# PX4FMUv1_6.net
KiCad netlist of a schematic drawn in EAGLE
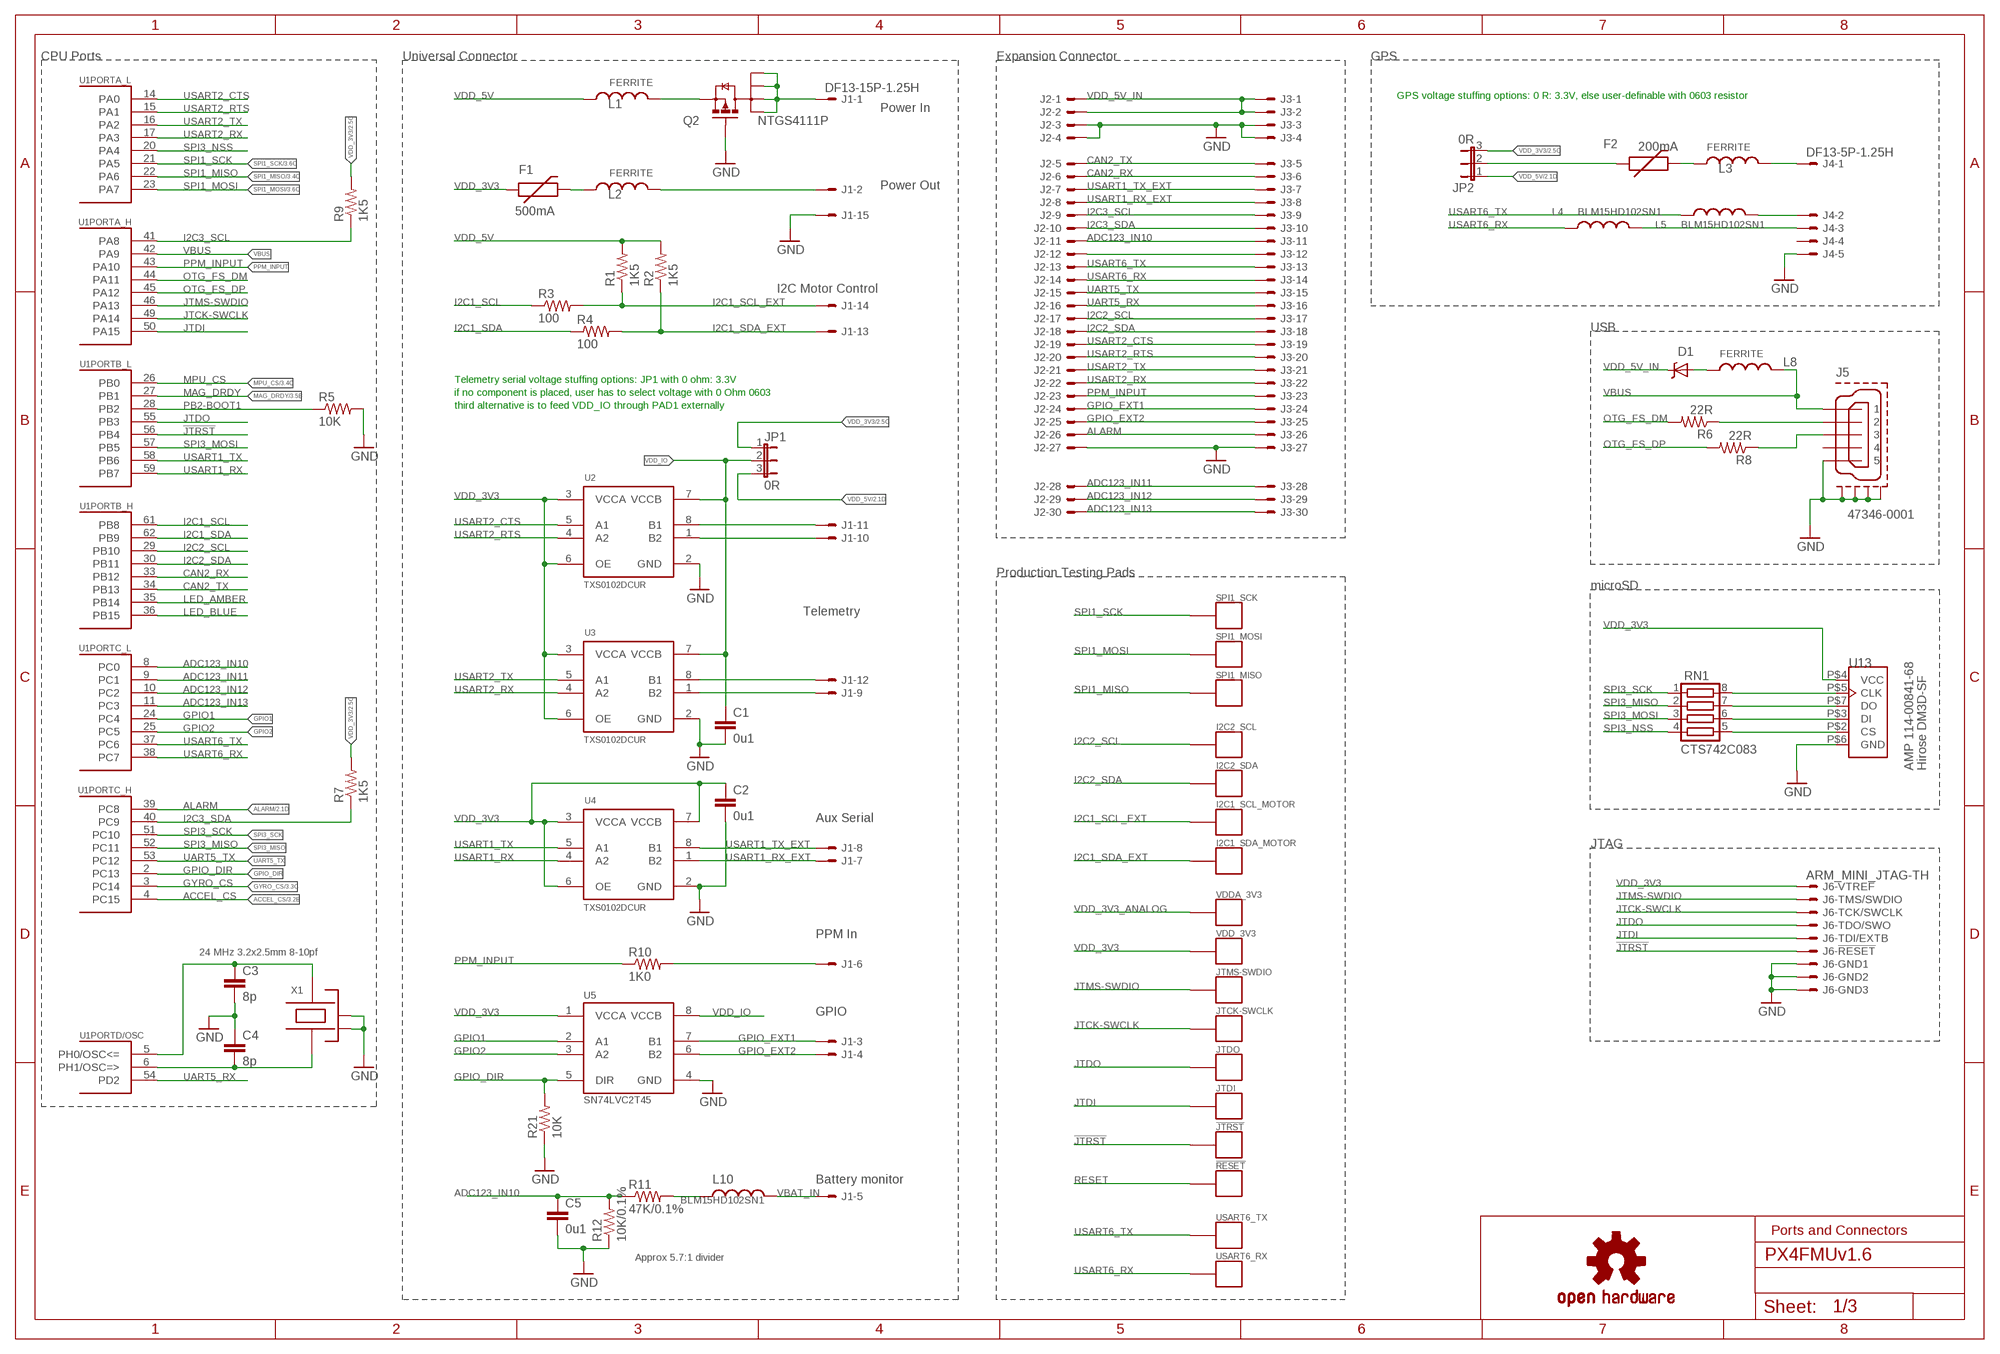
[diagram p0: schematic, sheet 1]
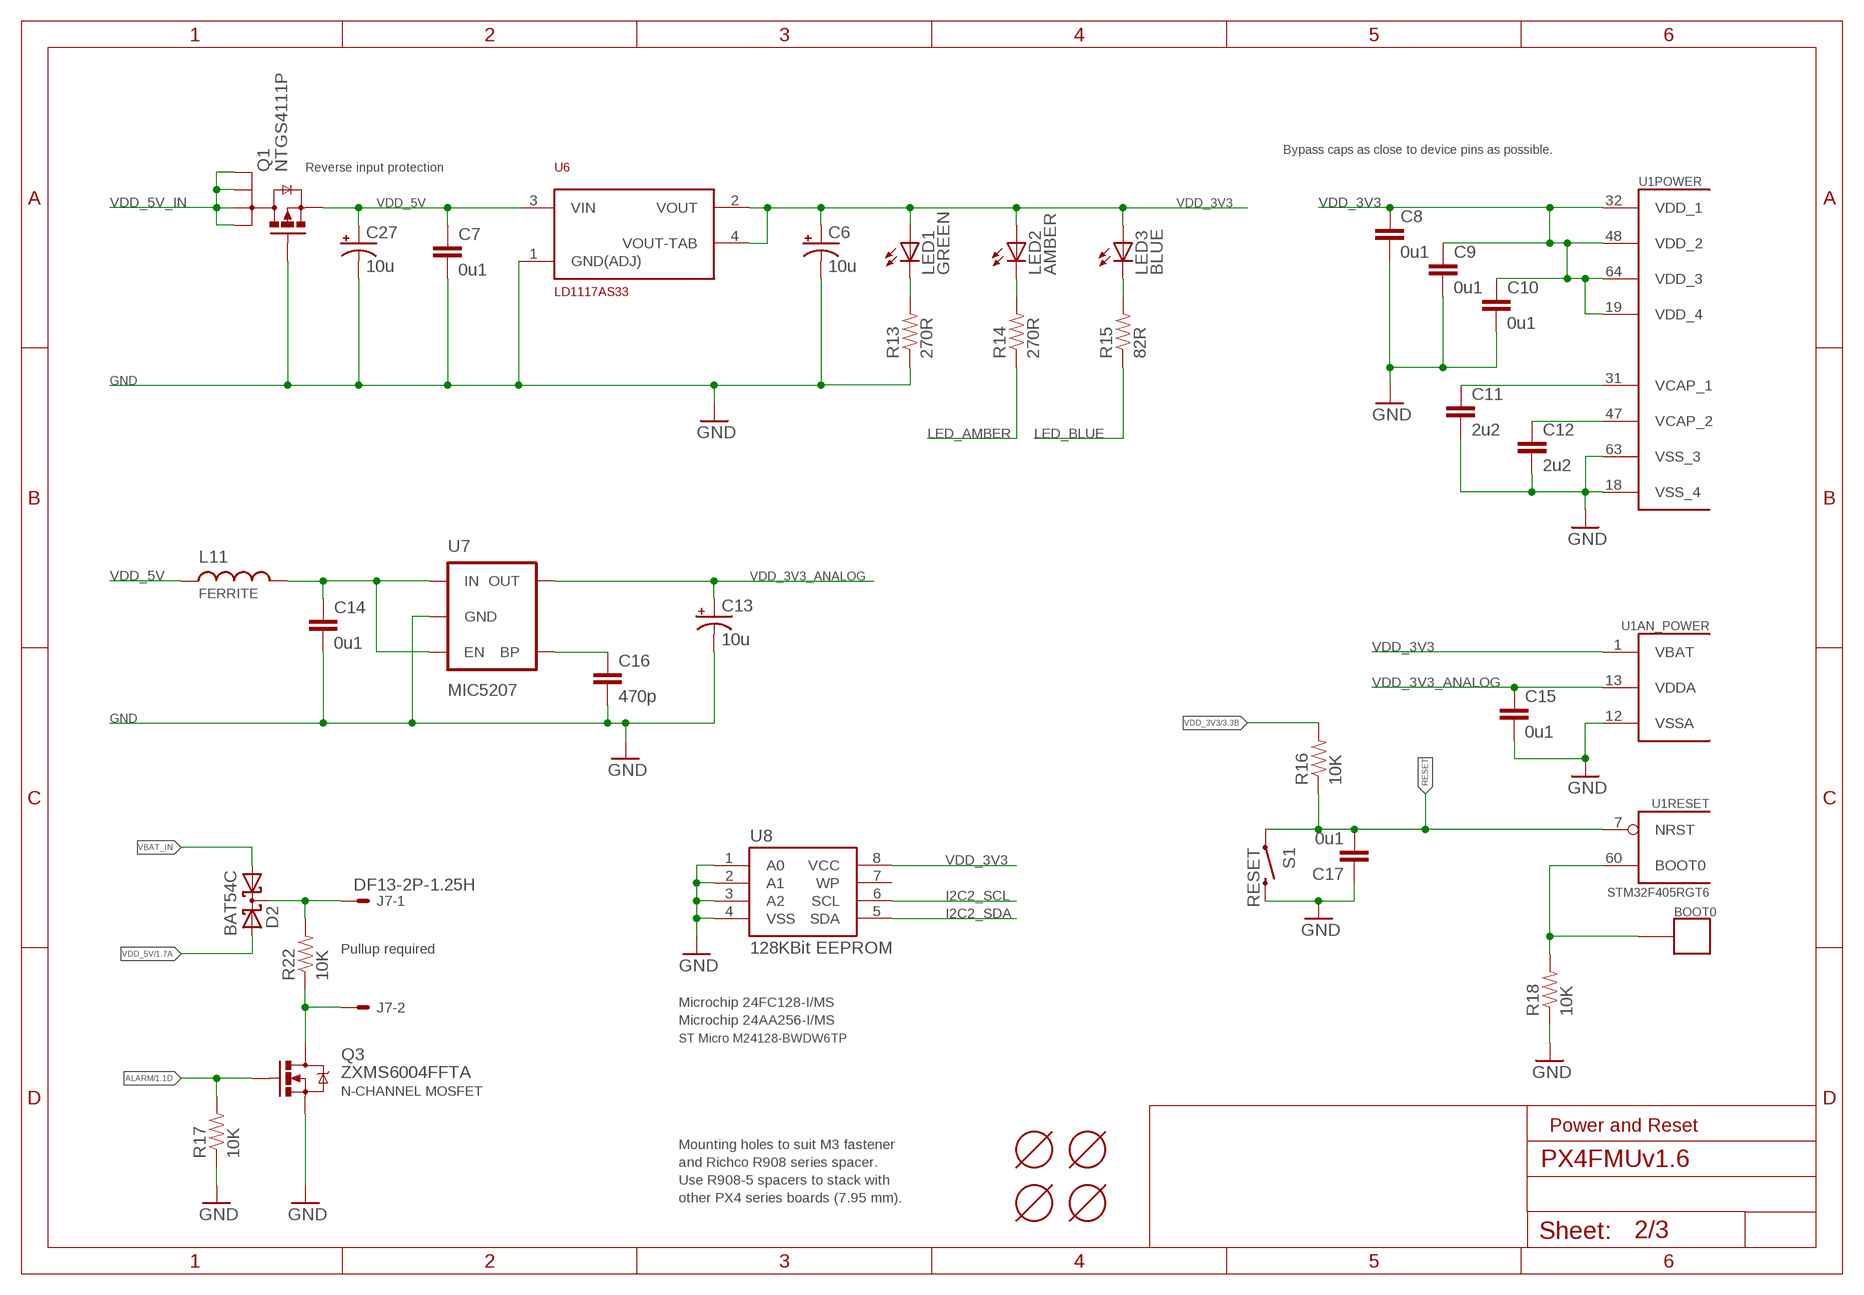
[diagram p1: schematic, sheet 2]
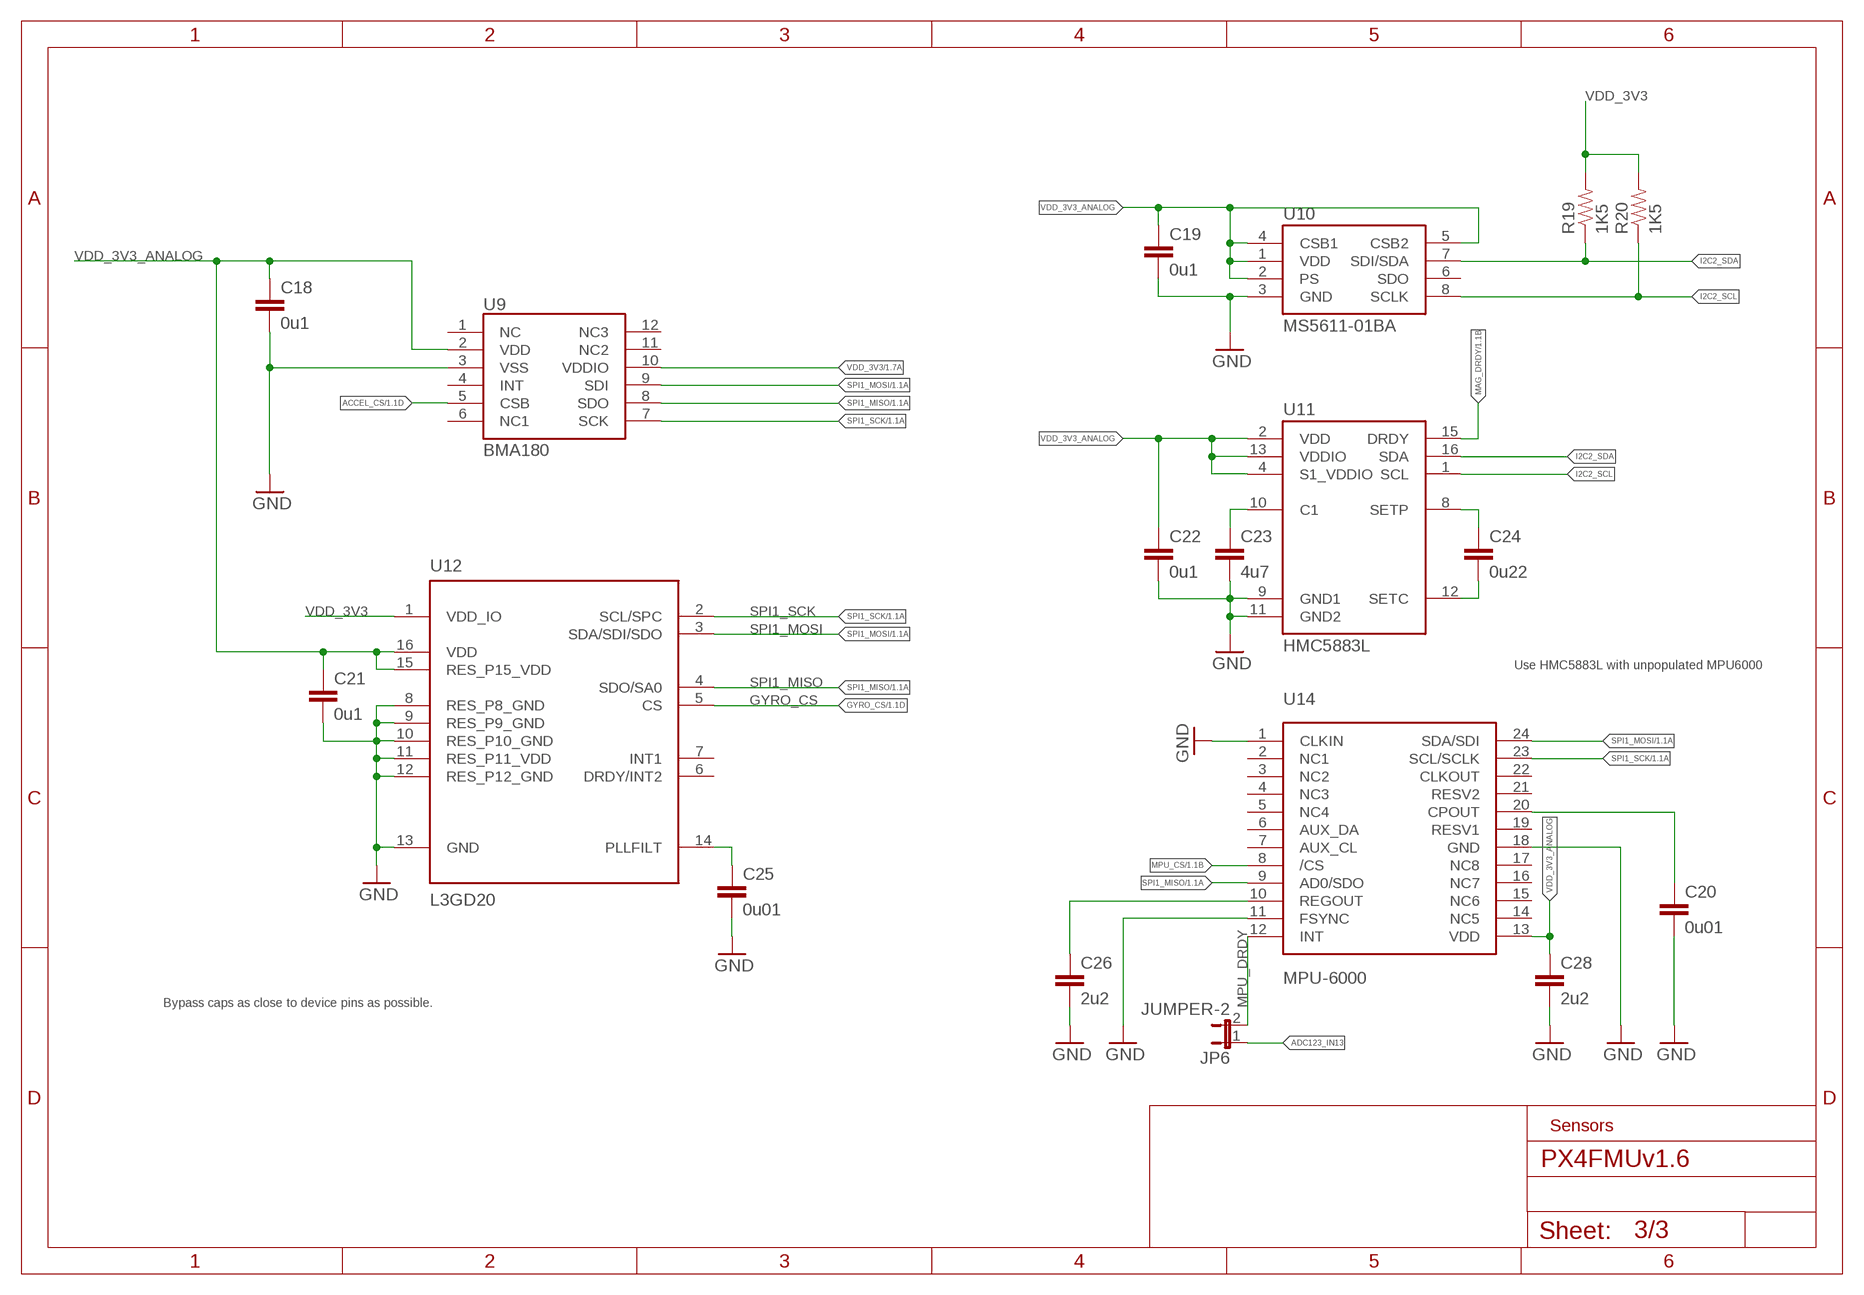
[diagram p2: schematic, sheet 3]

(export (version "E")
  (design (tool "Eeschema 10.0.6"))
  (components
    (comp (ref "!JTRST")
      (value "PAD.04")
      (footprint "eagle-import:PAD.04X.04")
      (libsource (lib "eagle-import") (part "PAD.04"))
    )
    (comp (ref "!RESET")
      (value "PAD.04")
      (footprint "eagle-import:PAD.04X.04")
      (libsource (lib "eagle-import") (part "PAD.04"))
    )
    (comp (ref "C1")
      (value "0u1")
      (footprint "eagle-import:0402-CAP")
      (fields (field (name "PARTNO") "CC0402ZRY5V7BB104"))
      (libsource (lib "eagle-import") (part "CAP0402-CAP"))
    )
    (comp (ref "C2")
      (value "0u1")
      (footprint "eagle-import:0402-CAP")
      (fields (field (name "PARTNO") "CC0402ZRY5V7BB104"))
      (libsource (lib "eagle-import") (part "CAP0402-CAP"))
    )
    (comp (ref "C3")
      (value "8p")
      (footprint "eagle-import:0402-CAP")
      (fields (field (name "PARTNO") "C1005C0G1H080C"))
      (libsource (lib "eagle-import") (part "CAP0402-CAP"))
    )
    (comp (ref "C4")
      (value "8p")
      (footprint "eagle-import:0402-CAP")
      (fields (field (name "PARTNO") "C1005C0G1H080C"))
      (libsource (lib "eagle-import") (part "CAP0402-CAP"))
    )
    (comp (ref "C5")
      (value "0u1")
      (footprint "eagle-import:0402-CAP")
      (fields (field (name "PARTNO") "CC0402ZRY5V7BB104"))
      (libsource (lib "eagle-import") (part "CAP0402-CAP"))
    )
    (comp (ref "D1")
      (value "MSS1P4-M3")
      (footprint "eagle-import:MICROSMP")
      (fields (field (name "PARTNO") "MSS1P4-M3/89A"))
      (libsource (lib "eagle-import") (part "DIODE-SCHOTTKY_MSMP"))
    )
    (comp (ref "F1")
      (value "500mA")
      (footprint "eagle-import:0402-PTC")
      (fields (field (name "PARTNO") "MF-FSMF050X-2"))
      (libsource (lib "eagle-import") (part "PTC0402"))
    )
    (comp (ref "F2")
      (value "200mA")
      (footprint "eagle-import:0402-PTC")
      (fields (field (name "PARTNO") "MF-FSMF020X-2"))
      (libsource (lib "eagle-import") (part "PTC0402"))
    )
    (comp (ref "I2C1_SCL_MOTOR")
      (value "PAD.03")
      (footprint "eagle-import:PAD.03X.03")
      (libsource (lib "eagle-import") (part "PAD.03"))
    )
    (comp (ref "I2C1_SDA_MOTOR")
      (value "PAD.03")
      (footprint "eagle-import:PAD.03X.03")
      (libsource (lib "eagle-import") (part "PAD.03"))
    )
    (comp (ref "I2C2_SCL")
      (value "PAD.03")
      (footprint "eagle-import:PAD.03X.03")
      (libsource (lib "eagle-import") (part "PAD.03"))
    )
    (comp (ref "I2C2_SDA")
      (value "PAD.04")
      (footprint "eagle-import:PAD.04X.04")
      (libsource (lib "eagle-import") (part "PAD.04"))
    )
    (comp (ref "J1")
      (value "DF13-15P-1.25H")
      (footprint "eagle-import:DF13A-15P-1.25H")
      (fields (field (name "PARTNO") "DF13A-15P-1.25H(20)"))
      (libsource (lib "eagle-import") (part "DF13-15P-1.25?H"))
    )
    (comp (ref "J2")
      (value "HEADER_2X15-REV")
      (footprint "eagle-import:HEADER_2MM_2X15_REVERSE")
      (fields (field (name "BOM") "EXCLUDE") (field (name "PARTNO") "953230-2000-AR-PR"))
      (libsource (lib "eagle-import") (part "HEADER_2X15-REV"))
    )
    (comp (ref "J3")
      (value "HEADER_2X15")
      (footprint "eagle-import:HEADER_2MM_2X15")
      (fields (field (name "PARTNO") "953230-2000-AR-PR"))
      (libsource (lib "eagle-import") (part "HEADER_2X15-SMD"))
    )
    (comp (ref "J4")
      (value "DF13-5P-1.25H")
      (footprint "eagle-import:DF13A-5P-1.25H")
      (fields (field (name "PARTNO") "DF13A-5P-1.25H(20)"))
      (libsource (lib "eagle-import") (part "DF13-5P-1.25?H"))
    )
    (comp (ref "J5")
      (value "47346-0001")
      (footprint "eagle-import:MOLEX-47346-0001")
      (libsource (lib "eagle-import") (part "MOLEX-47346-0001"))
    )
    (comp (ref "J6")
      (value "ARM_MINI_JTAG-TH")
      (footprint "eagle-import:FTSH-105-01-XXX-DV")
      (fields (field (name "PARTNO") "M50-3900542"))
      (libsource (lib "eagle-import") (part "ARM_MINI_JTAG-TH"))
    )
    (comp (ref "JP1")
      (value "0R")
      (footprint "eagle-import:SJ_3_0603_PASTE1&2")
      (fields (field (name "PARTNO") "RMCF0402ZT0R00"))
      (libsource (lib "eagle-import") (part "JUMPER-30603"))
    )
    (comp (ref "JP2")
      (value "0R")
      (footprint "eagle-import:SJ_3_0603_PASTE1&2")
      (fields (field (name "PARTNO") "RMCF0402ZT0R00"))
      (libsource (lib "eagle-import") (part "JUMPER-30603"))
    )
    (comp (ref "JTCK-SWCLK")
      (value "PAD.04")
      (footprint "eagle-import:PAD.04X.04")
      (libsource (lib "eagle-import") (part "PAD.04"))
    )
    (comp (ref "JTDI")
      (value "PAD.04")
      (footprint "eagle-import:PAD.04X.04")
      (libsource (lib "eagle-import") (part "PAD.04"))
    )
    (comp (ref "JTDO")
      (value "PAD.04")
      (footprint "eagle-import:PAD.04X.04")
      (libsource (lib "eagle-import") (part "PAD.04"))
    )
    (comp (ref "JTMS-SWDIO")
      (value "PAD.04")
      (footprint "eagle-import:PAD.04X.04")
      (libsource (lib "eagle-import") (part "PAD.04"))
    )
    (comp (ref "L1")
      (value "FERRITE")
      (footprint "eagle-import:0402-IND")
      (fields (field (name "PARTNO") "BKP1005HS121-T"))
      (libsource (lib "eagle-import") (part "INDUCTOR0402"))
    )
    (comp (ref "L2")
      (value "FERRITE")
      (footprint "eagle-import:0402-IND")
      (fields (field (name "PARTNO") "BKP1005HS121-T"))
      (libsource (lib "eagle-import") (part "INDUCTOR0402"))
    )
    (comp (ref "L3")
      (value "FERRITE")
      (footprint "eagle-import:0402-IND")
      (fields (field (name "PARTNO") "BKP1005HS121-T"))
      (libsource (lib "eagle-import") (part "INDUCTOR0402"))
    )
    (comp (ref "L4")
      (value "BLM15HD102SN1")
      (footprint "eagle-import:0402-IND")
      (libsource (lib "eagle-import") (part "INDUCTOR0402"))
    )
    (comp (ref "L5")
      (value "BLM15HD102SN1")
      (footprint "eagle-import:0402-IND")
      (libsource (lib "eagle-import") (part "INDUCTOR0402"))
    )
    (comp (ref "L8")
      (value "FERRITE")
      (footprint "eagle-import:0402-IND")
      (fields (field (name "PARTNO") "BKP1005HS121-T"))
      (libsource (lib "eagle-import") (part "INDUCTOR0402"))
    )
    (comp (ref "L10")
      (value "BLM15HD102SN1")
      (footprint "eagle-import:0402-IND")
      (libsource (lib "eagle-import") (part "INDUCTOR0402"))
    )
    (comp (ref "Q2")
      (value "NTGS4111P")
      (footprint "eagle-import:TSOP-6")
      (libsource (lib "eagle-import") (part "NTGS4111P"))
    )
    (comp (ref "R1")
      (value "1K5")
      (footprint "eagle-import:0402-RES")
      (fields (field (name "PARTNO") "RMCF0402JT1K50"))
      (libsource (lib "eagle-import") (part "RESISTOR0402-RES"))
    )
    (comp (ref "R2")
      (value "1K5")
      (footprint "eagle-import:0402-RES")
      (fields (field (name "PARTNO") "RMCF0402JT1K50"))
      (libsource (lib "eagle-import") (part "RESISTOR0402-RES"))
    )
    (comp (ref "R3")
      (value "100")
      (footprint "eagle-import:0402-RES")
      (fields (field (name "PARTNO") "RMCF0402JT100R"))
      (libsource (lib "eagle-import") (part "RESISTOR0402-RES"))
    )
    (comp (ref "R4")
      (value "100")
      (footprint "eagle-import:0402-RES")
      (fields (field (name "PARTNO") "RMCF0402JT100R"))
      (libsource (lib "eagle-import") (part "RESISTOR0402-RES"))
    )
    (comp (ref "R5")
      (value "10K")
      (footprint "eagle-import:0402-RES")
      (fields (field (name "PARTNO") "RMCF0402FT10K0"))
      (libsource (lib "eagle-import") (part "RESISTOR0402-RES"))
    )
    (comp (ref "R6")
      (value "22R")
      (footprint "eagle-import:0402-RES")
      (fields (field (name "PARTNO") "RMCF0402JT22R0"))
      (libsource (lib "eagle-import") (part "RESISTOR0402-RES"))
    )
    (comp (ref "R7")
      (value "1K5")
      (footprint "eagle-import:0402-RES")
      (fields (field (name "PARTNO") "RMCF0402JT1K50"))
      (libsource (lib "eagle-import") (part "RESISTOR0402-RES"))
    )
    (comp (ref "R8")
      (value "22R")
      (footprint "eagle-import:0402-RES")
      (fields (field (name "PARTNO") "RMCF0402JT22R0"))
      (libsource (lib "eagle-import") (part "RESISTOR0402-RES"))
    )
    (comp (ref "R9")
      (value "1K5")
      (footprint "eagle-import:0402-RES")
      (fields (field (name "PARTNO") "RMCF0402JT1K50"))
      (libsource (lib "eagle-import") (part "RESISTOR0402-RES"))
    )
    (comp (ref "R10")
      (value "1K0")
      (footprint "eagle-import:0402-RES")
      (fields (field (name "PARTNO") "RMCF0402JT1K00"))
      (libsource (lib "eagle-import") (part "RESISTOR0402-RES"))
    )
    (comp (ref "R11")
      (value "47K/0.1%")
      (footprint "eagle-import:0402-RES")
      (fields (field (name "PARTNO") "ERA-2AEB473X"))
      (libsource (lib "eagle-import") (part "RESISTOR0402-RES"))
    )
    (comp (ref "R12")
      (value "10K/0.1%")
      (footprint "eagle-import:0402-RES")
      (fields (field (name "PARTNO") "ERA-2AEB103X"))
      (libsource (lib "eagle-import") (part "RESISTOR0402-RES"))
    )
    (comp (ref "R21")
      (value "10K")
      (footprint "eagle-import:0402-RES")
      (fields (field (name "PARTNO") "RMCF0402FT10K0"))
      (libsource (lib "eagle-import") (part "RESISTOR0402-RES"))
    )
    (comp (ref "RN1")
      (value "CTS742C083")
      (footprint "eagle-import:CTS742C083")
      (fields (field (name "PARTNO") "TC164-JR-07100RL"))
      (libsource (lib "eagle-import") (part "CTS742C083"))
    )
    (comp (ref "SPI1_MISO")
      (value "PAD.04")
      (footprint "eagle-import:PAD.04X.04")
      (libsource (lib "eagle-import") (part "PAD.04"))
    )
    (comp (ref "SPI1_MOSI")
      (value "PAD.04")
      (footprint "eagle-import:PAD.04X.04")
      (libsource (lib "eagle-import") (part "PAD.04"))
    )
    (comp (ref "SPI1_SCK")
      (value "PAD.04")
      (footprint "eagle-import:PAD.04X.04")
      (libsource (lib "eagle-import") (part "PAD.04"))
    )
    (comp (ref "U$7")
      (value "OSHW-LOGOS")
      (footprint "eagle-import:OSHW-LOGO-S")
      (libsource (lib "eagle-import") (part "OSHW-LOGOS"))
    )
    (comp (ref "U1")
      (value "STM32F405RGT6")
      (footprint "eagle-import:TQFP64")
      (fields (field (name "PARTNO") "STM32F405RGT6"))
      (libsource (lib "eagle-import") (part "STM32F20X_TQFP64"))
    )
    (comp (ref "U2")
      (value "TXS0102DCUR")
      (footprint "eagle-import:TI-DCU")
      (libsource (lib "eagle-import") (part "TXS0102DCUR"))
    )
    (comp (ref "U3")
      (value "TXS0102DCUR")
      (footprint "eagle-import:TI-DCU")
      (libsource (lib "eagle-import") (part "TXS0102DCUR"))
    )
    (comp (ref "U4")
      (value "TXS0102DCUR")
      (footprint "eagle-import:TI-DCU")
      (libsource (lib "eagle-import") (part "TXS0102DCUR"))
    )
    (comp (ref "U5")
      (value "SN74LVC2T45")
      (footprint "eagle-import:TI-DCU")
      (libsource (lib "eagle-import") (part "SN74LVC2T45DCUR"))
    )
    (comp (ref "U13")
      (value "AMP 114-00841-68")
      (footprint "eagle-import:AMPHENOL_114-00841-68")
      (fields (field (name "PARTNO") "114-00841-68"))
      (libsource (lib "eagle-import") (part "SF-MICROSDAMP-114-00841-68"))
    )
    (comp (ref "USART6_RX")
      (value "PAD.04")
      (footprint "eagle-import:PAD.04X.04")
      (libsource (lib "eagle-import") (part "PAD.04"))
    )
    (comp (ref "USART6_TX")
      (value "PAD.04")
      (footprint "eagle-import:PAD.04X.04")
      (libsource (lib "eagle-import") (part "PAD.04"))
    )
    (comp (ref "VDDA_3V3")
      (value "PAD.04")
      (footprint "eagle-import:PAD.04X.04")
      (libsource (lib "eagle-import") (part "PAD.04"))
    )
    (comp (ref "VDD_3V3")
      (value "PAD.04")
      (footprint "eagle-import:PAD.04X.04")
      (libsource (lib "eagle-import") (part "PAD.04"))
    )
    (comp (ref "X1")
      (value "24 MHz 3.2x2.5mm 8-10pf")
      (footprint "eagle-import:OSCILLATOR-3.2X2.5")
      (fields (field (name "PARTNO") "NX3225SA-24.000000MHZ"))
      (libsource (lib "eagle-import") (part "OSCILLATOR-3.2X2.5"))
    )
    (comp (ref "C18")
      (value "0u1")
      (footprint "eagle-import:0402-CAP")
      (fields (field (name "PARTNO") "CC0402ZRY5V7BB104"))
      (libsource (lib "eagle-import") (part "CAP0402-CAP"))
    )
    (comp (ref "C19")
      (value "0u1")
      (footprint "eagle-import:0402-CAP")
      (fields (field (name "PARTNO") "CC0402ZRY5V7BB104"))
      (libsource (lib "eagle-import") (part "CAP0402-CAP"))
    )
    (comp (ref "C20")
      (value "0u01")
      (footprint "eagle-import:0402-CAP")
      (fields (field (name "PARTNO") "CC0402KRX7R7BB103"))
      (libsource (lib "eagle-import") (part "CAP0402-CAP"))
    )
    (comp (ref "C21")
      (value "0u1")
      (footprint "eagle-import:0402-CAP")
      (fields (field (name "PARTNO") "CC0402ZRY5V7BB104"))
      (libsource (lib "eagle-import") (part "CAP0402-CAP"))
    )
    (comp (ref "C22")
      (value "0u1")
      (footprint "eagle-import:0402-CAP")
      (fields (field (name "PARTNO") "CC0402ZRY5V7BB104"))
      (libsource (lib "eagle-import") (part "CAP0402-CAP"))
    )
    (comp (ref "C23")
      (value "4u7")
      (footprint "eagle-import:0402-CAP")
      (fields (field (name "PARTNO") "C1608Y5V0J475Z"))
      (libsource (lib "eagle-import") (part "CAP0402-CAP"))
    )
    (comp (ref "C24")
      (value "0u22")
      (footprint "eagle-import:0402-CAP")
      (fields (field (name "PARTNO") "C1005Y5V1C224Z"))
      (libsource (lib "eagle-import") (part "CAP0402-CAP"))
    )
    (comp (ref "C25")
      (value "0u01")
      (footprint "eagle-import:0402-CAP")
      (fields (field (name "PARTNO") "CC0402KRX7R7BB103"))
      (libsource (lib "eagle-import") (part "CAP0402-CAP"))
    )
    (comp (ref "C26")
      (value "2u2")
      (footprint "eagle-import:0402-CAP")
      (fields (field (name "PARTNO") "C1608Y5V1C225Z"))
      (libsource (lib "eagle-import") (part "CAP0402-CAP"))
    )
    (comp (ref "C28")
      (value "2u2")
      (footprint "eagle-import:0402-CAP")
      (fields (field (name "PARTNO") "C1608Y5V1C225Z"))
      (libsource (lib "eagle-import") (part "CAP0402-CAP"))
    )
    (comp (ref "JP6")
      (value "JUMPER-2")
      (footprint "eagle-import:SJ_2")
      (libsource (lib "eagle-import") (part "JUMPER-2"))
    )
    (comp (ref "R19")
      (value "1K5")
      (footprint "eagle-import:0402-RES")
      (fields (field (name "PARTNO") "RMCF0402JT1K50"))
      (libsource (lib "eagle-import") (part "RESISTOR0402-RES"))
    )
    (comp (ref "R20")
      (value "1K5")
      (footprint "eagle-import:0402-RES")
      (fields (field (name "PARTNO") "RMCF0402JT1K50"))
      (libsource (lib "eagle-import") (part "RESISTOR0402-RES"))
    )
    (comp (ref "U9")
      (value "BMA180")
      (footprint "eagle-import:LGA12")
      (libsource (lib "eagle-import") (part "BMA180"))
    )
    (comp (ref "U10")
      (value "MS5611-01BA")
      (footprint "eagle-import:MS5611-01BA")
      (libsource (lib "eagle-import") (part "MS5611-01BA"))
    )
    (comp (ref "U11")
      (value "HMC5883L")
      (footprint "eagle-import:HMC5883L-MAN")
      (libsource (lib "eagle-import") (part "HMC5883L"))
    )
    (comp (ref "U12")
      (value "L3GD20")
      (footprint "eagle-import:L3G4200DH-MAN")
      (libsource (lib "eagle-import") (part "L3G4200DH-LL"))
    )
    (comp (ref "U14")
      (value "MPU-6000")
      (footprint "eagle-import:QFN-24")
      (libsource (lib "eagle-import") (part "MPU-6000"))
    )
    (comp (ref "BOOT0")
      (value "PAD.04")
      (footprint "eagle-import:PAD.04X.04")
      (libsource (lib "eagle-import") (part "PAD.04"))
    )
    (comp (ref "C6")
      (value "10u")
      (footprint "eagle-import:EIA3216")
      (fields (field (name "PARTNO") "F931A106MAA"))
      (libsource (lib "eagle-import") (part "CAP_POL1206"))
    )
    (comp (ref "C7")
      (value "0u1")
      (footprint "eagle-import:0402-CAP")
      (fields (field (name "PARTNO") "CC0402ZRY5V7BB104"))
      (libsource (lib "eagle-import") (part "CAP0402-CAP"))
    )
    (comp (ref "C8")
      (value "0u1")
      (footprint "eagle-import:0402-CAP")
      (fields (field (name "PARTNO") "CC0402ZRY5V7BB104"))
      (libsource (lib "eagle-import") (part "CAP0402-CAP"))
    )
    (comp (ref "C9")
      (value "0u1")
      (footprint "eagle-import:0402-CAP")
      (fields (field (name "PARTNO") "CC0402ZRY5V7BB104"))
      (libsource (lib "eagle-import") (part "CAP0402-CAP"))
    )
    (comp (ref "C10")
      (value "0u1")
      (footprint "eagle-import:0402-CAP")
      (fields (field (name "PARTNO") "CC0402ZRY5V7BB104"))
      (libsource (lib "eagle-import") (part "CAP0402-CAP"))
    )
    (comp (ref "C11")
      (value "2u2")
      (footprint "eagle-import:0402-CAP")
      (fields (field (name "PARTNO") "C1608Y5V1C225Z"))
      (libsource (lib "eagle-import") (part "CAP0402-CAP"))
    )
    (comp (ref "C12")
      (value "2u2")
      (footprint "eagle-import:0402-CAP")
      (fields (field (name "PARTNO") "C1608Y5V1C225Z"))
      (libsource (lib "eagle-import") (part "CAP0402-CAP"))
    )
    (comp (ref "C13")
      (value "10u")
      (footprint "eagle-import:EIA3216")
      (fields (field (name "PARTNO") "F931A106MAA"))
      (libsource (lib "eagle-import") (part "CAP_POL1206"))
    )
    (comp (ref "C14")
      (value "0u1")
      (footprint "eagle-import:0402-CAP")
      (fields (field (name "PARTNO") "CC0402ZRY5V7BB104"))
      (libsource (lib "eagle-import") (part "CAP0402-CAP"))
    )
    (comp (ref "C15")
      (value "0u1")
      (footprint "eagle-import:0402-CAP")
      (fields (field (name "PARTNO") "CC0402ZRY5V7BB104"))
      (libsource (lib "eagle-import") (part "CAP0402-CAP"))
    )
    (comp (ref "C16")
      (value "470p")
      (footprint "eagle-import:0402-CAP")
      (fields (field (name "PARTNO") "CC0402KRX7R9BB471"))
      (libsource (lib "eagle-import") (part "CAP0402-CAP"))
    )
    (comp (ref "C17")
      (value "0u1")
      (footprint "eagle-import:0402-CAP")
      (fields (field (name "PARTNO") "CC0402ZRY5V7BB104"))
      (libsource (lib "eagle-import") (part "CAP0402-CAP"))
    )
    (comp (ref "C27")
      (value "10u")
      (footprint "eagle-import:EIA3216")
      (fields (field (name "PARTNO") "F931A106MAA"))
      (libsource (lib "eagle-import") (part "CAP_POL1206"))
    )
    (comp (ref "D2")
      (value "BAT54C")
      (footprint "eagle-import:SOT23-3")
      (fields (field (name "PARTNO") "BAT54C-7-F"))
      (libsource (lib "eagle-import") (part "BAT54C"))
    )
    (comp (ref "J7")
      (value "DF13-2P-1.25H")
      (footprint "eagle-import:DF13A-2P-1.25H")
      (fields (field (name "PARTNO") "DF13-2P-1.25DSA"))
      (libsource (lib "eagle-import") (part "DF13-2P-1.25?H"))
    )
    (comp (ref "L11")
      (value "FERRITE")
      (footprint "eagle-import:0402-IND")
      (fields (field (name "PARTNO") "BKP1005HS121-T"))
      (libsource (lib "eagle-import") (part "INDUCTOR0402"))
    )
    (comp (ref "LED1")
      (value "GREEN")
      (footprint "eagle-import:LED-0603")
      (fields (field (name "PARTNO") "LNJ337W83RA"))
      (libsource (lib "eagle-import") (part "LED0603"))
    )
    (comp (ref "LED2")
      (value "AMBER")
      (footprint "eagle-import:LED-0603")
      (fields (field (name "PARTNO") "LNJ437W84RA"))
      (libsource (lib "eagle-import") (part "LED0603"))
    )
    (comp (ref "LED3")
      (value "BLUE")
      (footprint "eagle-import:LED-0603")
      (fields (field (name "PARTNO") "LNJ937W8CRA"))
      (libsource (lib "eagle-import") (part "LED0603"))
    )
    (comp (ref "Q1")
      (value "NTGS4111P")
      (footprint "eagle-import:TSOP-6")
      (libsource (lib "eagle-import") (part "NTGS4111P"))
    )
    (comp (ref "Q3")
      (value "ZXMS6004FFTA")
      (footprint "eagle-import:SOT23-3")
      (libsource (lib "eagle-import") (part "MOSFET-NCHANNELSMD"))
    )
    (comp (ref "R13")
      (value "270R")
      (footprint "eagle-import:0402-RES")
      (fields (field (name "PARTNO") "RC0402JR-07270RL"))
      (libsource (lib "eagle-import") (part "RESISTOR0402-RES"))
    )
    (comp (ref "R14")
      (value "270R")
      (footprint "eagle-import:0402-RES")
      (fields (field (name "PARTNO") "RC0402JR-07270RL"))
      (libsource (lib "eagle-import") (part "RESISTOR0402-RES"))
    )
    (comp (ref "R15")
      (value "82R")
      (footprint "eagle-import:0402-RES")
      (fields (field (name "PARTNO") "RC0402JR-0782RL"))
      (libsource (lib "eagle-import") (part "RESISTOR0402-RES"))
    )
    (comp (ref "R16")
      (value "10K")
      (footprint "eagle-import:0402-RES")
      (fields (field (name "PARTNO") "RMCF0402FT10K0"))
      (libsource (lib "eagle-import") (part "RESISTOR0402-RES"))
    )
    (comp (ref "R17")
      (value "10K")
      (footprint "eagle-import:0402-RES")
      (fields (field (name "PARTNO") "RMCF0402FT10K0"))
      (libsource (lib "eagle-import") (part "RESISTOR0402-RES"))
    )
    (comp (ref "R18")
      (value "10K")
      (footprint "eagle-import:0402-RES")
      (fields (field (name "PARTNO") "RMCF0402FT10K0"))
      (libsource (lib "eagle-import") (part "RESISTOR0402-RES"))
    )
    (comp (ref "R22")
      (value "10K")
      (footprint "eagle-import:0402-RES")
      (fields (field (name "PARTNO") "RMCF0402FT10K0"))
      (libsource (lib "eagle-import") (part "RESISTOR0402-RES"))
    )
    (comp (ref "S1")
      (value "RESET")
      (footprint "eagle-import:EVQP7J01K")
      (fields (field (name "PARTNO") "EVQP7J01K"))
      (libsource (lib "eagle-import") (part "SWITCH-MOMENTARY-2"))
    )
    (comp (ref "U$1")
      (value "MOUNT-HOLE3.1MM")
      (footprint "eagle-import:MOUNT-HOLE3.1")
      (libsource (lib "eagle-import") (part "MOUNT-HOLE3.1MM"))
    )
    (comp (ref "U$2")
      (value "MOUNT-HOLE3.1MM")
      (footprint "eagle-import:MOUNT-HOLE3.1")
      (libsource (lib "eagle-import") (part "MOUNT-HOLE3.1MM"))
    )
    (comp (ref "U$3")
      (value "MOUNT-HOLE3.1MM")
      (footprint "eagle-import:MOUNT-HOLE3.1")
      (libsource (lib "eagle-import") (part "MOUNT-HOLE3.1MM"))
    )
    (comp (ref "U$4")
      (value "MOUNT-HOLE3.1MM")
      (footprint "eagle-import:MOUNT-HOLE3.1")
      (libsource (lib "eagle-import") (part "MOUNT-HOLE3.1MM"))
    )
    (comp (ref "U6")
      (value "LD1117AS33")
      (footprint "eagle-import:SOT-223")
      (libsource (lib "eagle-import") (part "LD1117AS33"))
    )
    (comp (ref "U7")
      (value "MIC5207")
      (footprint "eagle-import:SOT23-5")
      (fields (field (name "PARTNO") "MIC5207-3.3YM5"))
      (libsource (lib "eagle-import") (part "V_REG_LDOSMD"))
    )
    (comp (ref "U8")
      (value "128KBit EEPROM")
      (footprint "eagle-import:MSOP-8")
      (fields (field (name "PARTNO") "24FC128-I/MS"))
      (libsource (lib "eagle-import") (part "EEPROM-I2CMSOP"))
    )
  )
  (nets
    (net (code "1") (name "ACCEL_CS") (class "Default")
      (node (ref "U1") (pin "4") (pinfunction "PC15_4") (pintype "bidirectional"))
      (node (ref "U9") (pin "5") (pinfunction "CSB_5") (pintype "bidirectional"))
    )
    (net (code "2") (name "ADC123_IN10") (class "Default")
      (node (ref "C5") (pin "1") (pinfunction "1_1") (pintype "passive"))
      (node (ref "J2") (pin "11") (pinfunction "S_11") (pintype "passive"))
      (node (ref "J3") (pin "11") (pinfunction "S_11") (pintype "passive"))
      (node (ref "R11") (pin "1") (pinfunction "1_1") (pintype "passive"))
      (node (ref "R12") (pin "2") (pinfunction "2_2") (pintype "passive"))
      (node (ref "U1") (pin "8") (pinfunction "PC0_8") (pintype "bidirectional"))
    )
    (net (code "3") (name "ADC123_IN11") (class "Default")
      (node (ref "J2") (pin "28") (pinfunction "S_28") (pintype "passive"))
      (node (ref "J3") (pin "28") (pinfunction "S_28") (pintype "passive"))
      (node (ref "U1") (pin "9") (pinfunction "PC1_9") (pintype "bidirectional"))
    )
    (net (code "4") (name "ADC123_IN12") (class "Default")
      (node (ref "J2") (pin "29") (pinfunction "S_29") (pintype "passive"))
      (node (ref "J3") (pin "29") (pinfunction "S_29") (pintype "passive"))
      (node (ref "U1") (pin "10") (pinfunction "PC2_10") (pintype "bidirectional"))
    )
    (net (code "5") (name "ADC123_IN13") (class "Default")
      (node (ref "J2") (pin "30") (pinfunction "S_30") (pintype "passive"))
      (node (ref "J3") (pin "30") (pinfunction "S_30") (pintype "passive"))
      (node (ref "JP6") (pin "1") (pinfunction "1_1") (pintype "passive"))
      (node (ref "U1") (pin "11") (pinfunction "PC3_11") (pintype "bidirectional"))
    )
    (net (code "6") (name "ALARM") (class "Default")
      (node (ref "J2") (pin "26") (pinfunction "S_26") (pintype "passive"))
      (node (ref "J3") (pin "26") (pinfunction "S_26") (pintype "passive"))
      (node (ref "Q3") (pin "1") (pinfunction "G_1") (pintype "passive"))
      (node (ref "R17") (pin "2") (pinfunction "2_2") (pintype "passive"))
      (node (ref "U1") (pin "39") (pinfunction "PC8_39") (pintype "bidirectional"))
    )
    (net (code "7") (name "CAN2_RX") (class "Default")
      (node (ref "J2") (pin "6") (pinfunction "S_6") (pintype "passive"))
      (node (ref "J3") (pin "6") (pinfunction "S_6") (pintype "passive"))
      (node (ref "U1") (pin "33") (pinfunction "PB12_33") (pintype "bidirectional"))
    )
    (net (code "8") (name "CAN2_TX") (class "Default")
      (node (ref "J2") (pin "5") (pinfunction "S_5") (pintype "passive"))
      (node (ref "J3") (pin "5") (pinfunction "S_5") (pintype "passive"))
      (node (ref "U1") (pin "34") (pinfunction "PB13_34") (pintype "bidirectional"))
    )
    (net (code "9") (name "GND") (class "Default")
      (node (ref "C1") (pin "2") (pinfunction "2_2") (pintype "passive"))
      (node (ref "C10") (pin "2") (pinfunction "2_2") (pintype "passive"))
      (node (ref "C11") (pin "2") (pinfunction "2_2") (pintype "passive"))
      (node (ref "C12") (pin "2") (pinfunction "2_2") (pintype "passive"))
      (node (ref "C13") (pin "C") (pinfunction "-_C") (pintype "passive"))
      (node (ref "C14") (pin "2") (pinfunction "2_2") (pintype "passive"))
      (node (ref "C15") (pin "2") (pinfunction "2_2") (pintype "passive"))
      (node (ref "C16") (pin "2") (pinfunction "2_2") (pintype "passive"))
      (node (ref "C17") (pin "1") (pinfunction "1_1") (pintype "passive"))
      (node (ref "C18") (pin "2") (pinfunction "2_2") (pintype "passive"))
      (node (ref "C19") (pin "2") (pinfunction "2_2") (pintype "passive"))
      (node (ref "C2") (pin "2") (pinfunction "2_2") (pintype "passive"))
      (node (ref "C20") (pin "2") (pinfunction "2_2") (pintype "passive"))
      (node (ref "C21") (pin "2") (pinfunction "2_2") (pintype "passive"))
      (node (ref "C22") (pin "2") (pinfunction "2_2") (pintype "passive"))
      (node (ref "C23") (pin "2") (pinfunction "2_2") (pintype "passive"))
      (node (ref "C25") (pin "2") (pinfunction "2_2") (pintype "passive"))
      (node (ref "C26") (pin "2") (pinfunction "2_2") (pintype "passive"))
      (node (ref "C27") (pin "C") (pinfunction "-_C") (pintype "passive"))
      (node (ref "C28") (pin "2") (pinfunction "2_2") (pintype "passive"))
      (node (ref "C3") (pin "2") (pinfunction "2_2") (pintype "passive"))
      (node (ref "C4") (pin "1") (pinfunction "1_1") (pintype "passive"))
      (node (ref "C5") (pin "2") (pinfunction "2_2") (pintype "passive"))
      (node (ref "C6") (pin "C") (pinfunction "-_C") (pintype "passive"))
      (node (ref "C7") (pin "2") (pinfunction "2_2") (pintype "passive"))
      (node (ref "C8") (pin "2") (pinfunction "2_2") (pintype "passive"))
      (node (ref "C9") (pin "2") (pinfunction "2_2") (pintype "passive"))
      (node (ref "J1") (pin "15") (pinfunction "S_15") (pintype "passive"))
      (node (ref "J2") (pin "27") (pinfunction "S_27") (pintype "passive"))
      (node (ref "J2") (pin "3") (pinfunction "S_3") (pintype "passive"))
      (node (ref "J2") (pin "4") (pinfunction "S_4") (pintype "passive"))
      (node (ref "J3") (pin "27") (pinfunction "S_27") (pintype "passive"))
      (node (ref "J3") (pin "3") (pinfunction "S_3") (pintype "passive"))
      (node (ref "J3") (pin "4") (pinfunction "S_4") (pintype "passive"))
      (node (ref "J4") (pin "5") (pinfunction "S_5") (pintype "passive"))
      (node (ref "J5") (pin "GND") (pinfunction "5_GND") (pintype "power_in"))
      (node (ref "J5") (pin "GND1") (pinfunction "GND1_GND1") (pintype "bidirectional"))
      (node (ref "J5") (pin "GND2") (pinfunction "GND2_GND2") (pintype "bidirectional"))
      (node (ref "J5") (pin "GND3") (pinfunction "GND3_GND3") (pintype "bidirectional"))
      (node (ref "J5") (pin "GND4") (pinfunction "GND4_GND4") (pintype "bidirectional"))
      (node (ref "J6") (pin "3") (pinfunction "S_3") (pintype "passive"))
      (node (ref "J6") (pin "5") (pinfunction "S_5") (pintype "passive"))
      (node (ref "J6") (pin "9") (pinfunction "S_9") (pintype "passive"))
      (node (ref "Q1") (pin "3") (pinfunction "G_3") (pintype "passive"))
      (node (ref "Q2") (pin "3") (pinfunction "G_3") (pintype "passive"))
      (node (ref "Q3") (pin "2") (pinfunction "S_2") (pintype "passive"))
      (node (ref "R12") (pin "1") (pinfunction "1_1") (pintype "passive"))
      (node (ref "R13") (pin "1") (pinfunction "1_1") (pintype "passive"))
      (node (ref "R17") (pin "1") (pinfunction "1_1") (pintype "passive"))
      (node (ref "R18") (pin "1") (pinfunction "1_1") (pintype "passive"))
      (node (ref "R21") (pin "1") (pinfunction "1_1") (pintype "passive"))
      (node (ref "R5") (pin "2") (pinfunction "2_2") (pintype "passive"))
      (node (ref "S1") (pin "B3") (pinfunction "2_B3") (pintype "passive"))
      (node (ref "U1") (pin "12") (pinfunction "VSSA_12") (pintype "power_in"))
      (node (ref "U1") (pin "18") (pinfunction "VSS_4_18") (pintype "power_in"))
      (node (ref "U1") (pin "63") (pinfunction "VSS_3_63") (pintype "power_in"))
      (node (ref "U10") (pin "3") (pinfunction "GND_3") (pintype "bidirectional"))
      (node (ref "U11") (pin "11") (pinfunction "GND2_11") (pintype "bidirectional"))
      (node (ref "U11") (pin "9") (pinfunction "GND1_9") (pintype "bidirectional"))
      (node (ref "U12") (pin "10") (pinfunction "RES_P10_GND_10") (pintype "bidirectional"))
      (node (ref "U12") (pin "11") (pinfunction "RES_P11_VDD_11") (pintype "bidirectional"))
      (node (ref "U12") (pin "12") (pinfunction "RES_P12_GND_12") (pintype "bidirectional"))
      (node (ref "U12") (pin "13") (pinfunction "GND_13") (pintype "bidirectional"))
      (node (ref "U12") (pin "8") (pinfunction "RES_P8_GND_8") (pintype "bidirectional"))
      (node (ref "U12") (pin "9") (pinfunction "RES_P9_GND_9") (pintype "bidirectional"))
      (node (ref "U13") (pin "P$6") (pinfunction "GND_P$6") (pintype "power_in"))
      (node (ref "U14") (pin "1") (pinfunction "CLKIN_1") (pintype "bidirectional"))
      (node (ref "U14") (pin "11") (pinfunction "FSYNC_11") (pintype "bidirectional"))
      (node (ref "U14") (pin "18") (pinfunction "GND_18") (pintype "bidirectional"))
      (node (ref "U2") (pin "2") (pinfunction "GND_2") (pintype "power_in"))
      (node (ref "U3") (pin "2") (pinfunction "GND_2") (pintype "power_in"))
      (node (ref "U4") (pin "2") (pinfunction "GND_2") (pintype "power_in"))
      (node (ref "U5") (pin "4") (pinfunction "GND_4") (pintype "power_in"))
      (node (ref "U6") (pin "1") (pinfunction "GND(ADJ)_1") (pintype "bidirectional"))
      (node (ref "U7") (pin "2") (pinfunction "GND_2") (pintype "input"))
      (node (ref "U8") (pin "1") (pinfunction "A0_1") (pintype "bidirectional"))
      (node (ref "U8") (pin "2") (pinfunction "A1_2") (pintype "bidirectional"))
      (node (ref "U8") (pin "3") (pinfunction "A2_3") (pintype "bidirectional"))
      (node (ref "U8") (pin "4") (pinfunction "VSS_4") (pintype "power_in"))
      (node (ref "U9") (pin "3") (pinfunction "VSS_3") (pintype "bidirectional"))
      (node (ref "X1") (pin "2") (pinfunction "NC_2_2") (pintype "power_in"))
      (node (ref "X1") (pin "4") (pinfunction "NC_4_4") (pintype "power_in"))
    )
    (net (code "10") (name "GPIO1") (class "Default")
      (node (ref "U1") (pin "24") (pinfunction "PC4_24") (pintype "bidirectional"))
      (node (ref "U5") (pin "2") (pinfunction "A1_2") (pintype "bidirectional"))
    )
    (net (code "11") (name "GPIO2") (class "Default")
      (node (ref "U1") (pin "25") (pinfunction "PC5_25") (pintype "bidirectional"))
      (node (ref "U5") (pin "3") (pinfunction "A2_3") (pintype "bidirectional"))
    )
    (net (code "12") (name "GPIO_DIR") (class "Default")
      (node (ref "R21") (pin "2") (pinfunction "2_2") (pintype "passive"))
      (node (ref "U1") (pin "2") (pinfunction "PC13_2") (pintype "bidirectional"))
      (node (ref "U5") (pin "5") (pinfunction "DIR_5") (pintype "input"))
    )
    (net (code "13") (name "GPIO_EXT1") (class "Default")
      (node (ref "J1") (pin "3") (pinfunction "S_3") (pintype "passive"))
      (node (ref "J2") (pin "24") (pinfunction "S_24") (pintype "passive"))
      (node (ref "J3") (pin "24") (pinfunction "S_24") (pintype "passive"))
      (node (ref "U5") (pin "7") (pinfunction "B1_7") (pintype "bidirectional"))
    )
    (net (code "14") (name "GPIO_EXT2") (class "Default")
      (node (ref "J1") (pin "4") (pinfunction "S_4") (pintype "passive"))
      (node (ref "J2") (pin "25") (pinfunction "S_25") (pintype "passive"))
      (node (ref "J3") (pin "25") (pinfunction "S_25") (pintype "passive"))
      (node (ref "U5") (pin "6") (pinfunction "B2_6") (pintype "bidirectional"))
    )
    (net (code "15") (name "GYRO_CS") (class "Default")
      (node (ref "U1") (pin "3") (pinfunction "PC14_3") (pintype "bidirectional"))
      (node (ref "U12") (pin "5") (pinfunction "CS_5") (pintype "input"))
    )
    (net (code "16") (name "I2C1_SCL") (class "Default")
      (node (ref "R3") (pin "1") (pinfunction "1_1") (pintype "passive"))
      (node (ref "U1") (pin "61") (pinfunction "PB8_61") (pintype "bidirectional"))
    )
    (net (code "17") (name "I2C1_SCL_EXT") (class "Default")
      (node (ref "I2C1_SCL_MOTOR") (pin "P$1") (pinfunction "P$1_P$1") (pintype "passive"))
      (node (ref "J1") (pin "14") (pinfunction "S_14") (pintype "passive"))
      (node (ref "R1") (pin "1") (pinfunction "1_1") (pintype "passive"))
      (node (ref "R3") (pin "2") (pinfunction "2_2") (pintype "passive"))
    )
    (net (code "18") (name "I2C1_SDA") (class "Default")
      (node (ref "R4") (pin "1") (pinfunction "1_1") (pintype "passive"))
      (node (ref "U1") (pin "62") (pinfunction "PB9_62") (pintype "bidirectional"))
    )
    (net (code "19") (name "I2C1_SDA_EXT") (class "Default")
      (node (ref "I2C1_SDA_MOTOR") (pin "P$1") (pinfunction "P$1_P$1") (pintype "passive"))
      (node (ref "J1") (pin "13") (pinfunction "S_13") (pintype "passive"))
      (node (ref "R2") (pin "1") (pinfunction "1_1") (pintype "passive"))
      (node (ref "R4") (pin "2") (pinfunction "2_2") (pintype "passive"))
    )
    (net (code "20") (name "I2C2_SCL") (class "Default")
      (node (ref "I2C2_SCL") (pin "P$1") (pinfunction "P$1_P$1") (pintype "passive"))
      (node (ref "J2") (pin "17") (pinfunction "S_17") (pintype "passive"))
      (node (ref "J3") (pin "17") (pinfunction "S_17") (pintype "passive"))
      (node (ref "R20") (pin "1") (pinfunction "1_1") (pintype "passive"))
      (node (ref "U1") (pin "29") (pinfunction "PB10_29") (pintype "bidirectional"))
      (node (ref "U10") (pin "8") (pinfunction "SCLK_8") (pintype "bidirectional"))
      (node (ref "U11") (pin "1") (pinfunction "SCL_1") (pintype "bidirectional"))
      (node (ref "U8") (pin "6") (pinfunction "SCL_6") (pintype "bidirectional"))
    )
    (net (code "21") (name "I2C2_SDA") (class "Default")
      (node (ref "I2C2_SDA") (pin "P$1") (pinfunction "P$1_P$1") (pintype "passive"))
      (node (ref "J2") (pin "18") (pinfunction "S_18") (pintype "passive"))
      (node (ref "J3") (pin "18") (pinfunction "S_18") (pintype "passive"))
      (node (ref "R19") (pin "1") (pinfunction "1_1") (pintype "passive"))
      (node (ref "U1") (pin "30") (pinfunction "PB11_30") (pintype "bidirectional"))
      (node (ref "U10") (pin "7") (pinfunction "SDI/SDA_7") (pintype "bidirectional"))
      (node (ref "U11") (pin "16") (pinfunction "SDA_16") (pintype "bidirectional"))
      (node (ref "U8") (pin "5") (pinfunction "SDA_5") (pintype "bidirectional"))
    )
    (net (code "22") (name "I2C3_SCL") (class "Default")
      (node (ref "J2") (pin "9") (pinfunction "S_9") (pintype "passive"))
      (node (ref "J3") (pin "9") (pinfunction "S_9") (pintype "passive"))
      (node (ref "R9") (pin "1") (pinfunction "1_1") (pintype "passive"))
      (node (ref "U1") (pin "41") (pinfunction "PA8_41") (pintype "bidirectional"))
    )
    (net (code "23") (name "I2C3_SDA") (class "Default")
      (node (ref "J2") (pin "10") (pinfunction "S_10") (pintype "passive"))
      (node (ref "J3") (pin "10") (pinfunction "S_10") (pintype "passive"))
      (node (ref "R7") (pin "1") (pinfunction "1_1") (pintype "passive"))
      (node (ref "U1") (pin "40") (pinfunction "PC9_40") (pintype "bidirectional"))
    )
    (net (code "24") (name "JTCK-SWCLK") (class "Default")
      (node (ref "J6") (pin "4") (pinfunction "S_4") (pintype "passive"))
      (node (ref "JTCK-SWCLK") (pin "P$1") (pinfunction "P$1_P$1") (pintype "passive"))
      (node (ref "U1") (pin "49") (pinfunction "PA14_49") (pintype "bidirectional"))
    )
    (net (code "25") (name "JTDI") (class "Default")
      (node (ref "J6") (pin "8") (pinfunction "S_8") (pintype "passive"))
      (node (ref "JTDI") (pin "P$1") (pinfunction "P$1_P$1") (pintype "passive"))
      (node (ref "U1") (pin "50") (pinfunction "PA15_50") (pintype "bidirectional"))
    )
    (net (code "26") (name "JTDO") (class "Default")
      (node (ref "J6") (pin "6") (pinfunction "S_6") (pintype "passive"))
      (node (ref "JTDO") (pin "P$1") (pinfunction "P$1_P$1") (pintype "passive"))
      (node (ref "U1") (pin "55") (pinfunction "PB3_55") (pintype "bidirectional"))
    )
    (net (code "27") (name "JTMS-SWDIO") (class "Default")
      (node (ref "J6") (pin "2") (pinfunction "S_2") (pintype "passive"))
      (node (ref "JTMS-SWDIO") (pin "P$1") (pinfunction "P$1_P$1") (pintype "passive"))
      (node (ref "U1") (pin "46") (pinfunction "PA13_46") (pintype "bidirectional"))
    )
    (net (code "28") (name "LED_AMBER") (class "Default")
      (node (ref "R14") (pin "1") (pinfunction "1_1") (pintype "passive"))
      (node (ref "U1") (pin "35") (pinfunction "PB14_35") (pintype "bidirectional"))
    )
    (net (code "29") (name "LED_BLUE") (class "Default")
      (node (ref "R15") (pin "1") (pinfunction "1_1") (pintype "passive"))
      (node (ref "U1") (pin "36") (pinfunction "PB15_36") (pintype "bidirectional"))
    )
    (net (code "30") (name "MAG_DRDY") (class "Default")
      (node (ref "U1") (pin "27") (pinfunction "PB1_27") (pintype "bidirectional"))
      (node (ref "U11") (pin "15") (pinfunction "DRDY_15") (pintype "bidirectional"))
    )
    (net (code "31") (name "MPU_CS") (class "Default")
      (node (ref "U1") (pin "26") (pinfunction "PB0_26") (pintype "bidirectional"))
      (node (ref "U14") (pin "8") (pinfunction "/CS_8") (pintype "bidirectional"))
    )
    (net (code "32") (name "Net-(D1-A)") (class "Default")
      (node (ref "D1") (pin "ANODE") (pinfunction "A_ANODE") (pintype "passive"))
      (node (ref "L8") (pin "1") (pinfunction "1_1") (pintype "passive"))
    )
    (net (code "33") (name "Net-(D2-CC)") (class "Default")
      (node (ref "D2") (pin "3") (pinfunction "CC_3") (pintype "passive"))
      (node (ref "J7") (pin "1") (pinfunction "S_1") (pintype "passive"))
      (node (ref "R22") (pin "2") (pinfunction "2_2") (pintype "passive"))
    )
    (net (code "34") (name "Net-(F1-Pad2)") (class "Default")
      (node (ref "F1") (pin "2") (pinfunction "2_2") (pintype "bidirectional"))
      (node (ref "L2") (pin "1") (pinfunction "1_1") (pintype "passive"))
    )
    (net (code "35") (name "Net-(F2-Pad1)") (class "Default")
      (node (ref "F2") (pin "1") (pinfunction "1_1") (pintype "bidirectional"))
      (node (ref "JP2") (pin "2") (pinfunction "2_2") (pintype "passive"))
    )
    (net (code "36") (name "Net-(F2-Pad2)") (class "Default")
      (node (ref "F2") (pin "2") (pinfunction "2_2") (pintype "bidirectional"))
      (node (ref "L3") (pin "1") (pinfunction "1_1") (pintype "passive"))
    )
    (net (code "37") (name "Net-(J1A-S)") (class "Default")
      (node (ref "J1") (pin "1") (pinfunction "S_1") (pintype "passive"))
      (node (ref "Q2") (pin "1") (pinfunction "D_1") (pintype "passive"))
      (node (ref "Q2") (pin "2") (pinfunction "D1_2") (pintype "passive"))
      (node (ref "Q2") (pin "5") (pinfunction "D2_5") (pintype "passive"))
      (node (ref "Q2") (pin "6") (pinfunction "D3_6") (pintype "passive"))
    )
    (net (code "38") (name "Net-(J1B-S)") (class "Default")
      (node (ref "J1") (pin "10") (pinfunction "S_10") (pintype "passive"))
      (node (ref "U2") (pin "1") (pinfunction "B2_1") (pintype "bidirectional"))
    )
    (net (code "39") (name "Net-(J1C-S)") (class "Default")
      (node (ref "J1") (pin "11") (pinfunction "S_11") (pintype "passive"))
      (node (ref "U2") (pin "8") (pinfunction "B1_8") (pintype "bidirectional"))
    )
    (net (code "40") (name "Net-(J1D-S)") (class "Default")
      (node (ref "J1") (pin "12") (pinfunction "S_12") (pintype "passive"))
      (node (ref "U3") (pin "8") (pinfunction "B1_8") (pintype "bidirectional"))
    )
    (net (code "41") (name "Net-(J1H-S)") (class "Default")
      (node (ref "J1") (pin "2") (pinfunction "S_2") (pintype "passive"))
      (node (ref "L2") (pin "2") (pinfunction "2_2") (pintype "passive"))
    )
    (net (code "42") (name "Net-(J1L-S)") (class "Default")
      (node (ref "J1") (pin "6") (pinfunction "S_6") (pintype "passive"))
      (node (ref "R10") (pin "2") (pinfunction "2_2") (pintype "passive"))
    )
    (net (code "43") (name "Net-(J1O-S)") (class "Default")
      (node (ref "J1") (pin "9") (pinfunction "S_9") (pintype "passive"))
      (node (ref "U3") (pin "1") (pinfunction "B2_1") (pintype "bidirectional"))
    )
    (net (code "44") (name "Net-(J2D-S)") (class "Default")
      (node (ref "J2") (pin "12") (pinfunction "S_12") (pintype "passive"))
      (node (ref "J3") (pin "12") (pinfunction "S_12") (pintype "passive"))
    )
    (net (code "45") (name "Net-(J4A-S)") (class "Default")
      (node (ref "J4") (pin "1") (pinfunction "S_1") (pintype "passive"))
      (node (ref "L3") (pin "2") (pinfunction "2_2") (pintype "passive"))
    )
    (net (code "46") (name "Net-(J4B-S)") (class "Default")
      (node (ref "J4") (pin "2") (pinfunction "S_2") (pintype "passive"))
      (node (ref "L5") (pin "2") (pinfunction "2_2") (pintype "passive"))
    )
    (net (code "47") (name "Net-(J4C-S)") (class "Default")
      (node (ref "J4") (pin "3") (pinfunction "S_3") (pintype "passive"))
      (node (ref "L4") (pin "2") (pinfunction "2_2") (pintype "passive"))
    )
    (net (code "48") (name "Net-(J5-2)") (class "Default")
      (node (ref "J5") (pin "D-") (pinfunction "2_D-") (pintype "bidirectional"))
      (node (ref "R6") (pin "1") (pinfunction "1_1") (pintype "passive"))
    )
    (net (code "49") (name "Net-(J5-3)") (class "Default")
      (node (ref "J5") (pin "D+") (pinfunction "3_D+") (pintype "bidirectional"))
      (node (ref "R8") (pin "1") (pinfunction "1_1") (pintype "passive"))
    )
    (net (code "50") (name "Net-(J7B-S)") (class "Default")
      (node (ref "J7") (pin "2") (pinfunction "S_2") (pintype "passive"))
      (node (ref "Q3") (pin "3") (pinfunction "D_3") (pintype "passive"))
      (node (ref "R22") (pin "1") (pinfunction "1_1") (pintype "passive"))
    )
    (net (code "51") (name "Net-(L10-Pad1)") (class "Default")
      (node (ref "L10") (pin "1") (pinfunction "1_1") (pintype "passive"))
      (node (ref "R11") (pin "2") (pinfunction "2_2") (pintype "passive"))
    )
    (net (code "52") (name "Net-(LED1-PadC)") (class "Default")
      (node (ref "LED1") (pin "C") (pinfunction "C_C") (pintype "passive"))
      (node (ref "R13") (pin "2") (pinfunction "2_2") (pintype "passive"))
    )
    (net (code "53") (name "Net-(LED2-PadC)") (class "Default")
      (node (ref "LED2") (pin "C") (pinfunction "C_C") (pintype "passive"))
      (node (ref "R14") (pin "2") (pinfunction "2_2") (pintype "passive"))
    )
    (net (code "54") (name "Net-(LED3-PadC)") (class "Default")
      (node (ref "LED3") (pin "C") (pinfunction "C_C") (pintype "passive"))
      (node (ref "R15") (pin "2") (pinfunction "2_2") (pintype "passive"))
    )
    (net (code "55") (name "Net-(Q2-S)") (class "Default")
      (node (ref "L1") (pin "2") (pinfunction "2_2") (pintype "passive"))
      (node (ref "Q2") (pin "4") (pinfunction "S_4") (pintype "passive"))
    )
    (net (code "56") (name "Net-(U1H-PH0{slash}OSC<=)") (class "Default")
      (node (ref "C3") (pin "1") (pinfunction "1_1") (pintype "passive"))
      (node (ref "U1") (pin "5") (pinfunction "PH0/OSC<=_5") (pintype "bidirectional"))
      (node (ref "X1") (pin "3") (pinfunction "3_3") (pintype "bidirectional"))
    )
    (net (code "57") (name "Net-(U1H-PH1{slash}OSC=>)") (class "Default")
      (node (ref "C4") (pin "2") (pinfunction "2_2") (pintype "passive"))
      (node (ref "U1") (pin "6") (pinfunction "PH1/OSC=>_6") (pintype "bidirectional"))
      (node (ref "X1") (pin "1") (pinfunction "1_1") (pintype "bidirectional"))
    )
    (net (code "58") (name "Net-(U1I-VCAP_1)") (class "Default")
      (node (ref "C11") (pin "1") (pinfunction "1_1") (pintype "passive"))
      (node (ref "U1") (pin "31") (pinfunction "VCAP_1_31") (pintype "power_in"))
    )
    (net (code "59") (name "Net-(U1I-VCAP_2)") (class "Default")
      (node (ref "C12") (pin "1") (pinfunction "1_1") (pintype "passive"))
      (node (ref "U1") (pin "47") (pinfunction "VCAP_2_47") (pintype "power_in"))
    )
    (net (code "60") (name "Net-(U1J-BOOT0)") (class "Default")
      (node (ref "BOOT0") (pin "P$1") (pinfunction "P$1_P$1") (pintype "passive"))
      (node (ref "R18") (pin "2") (pinfunction "2_2") (pintype "passive"))
      (node (ref "U1") (pin "60") (pinfunction "BOOT0_60") (pintype "input"))
    )
    (net (code "61") (name "Net-(U7-BP)") (class "Default")
      (node (ref "C16") (pin "1") (pinfunction "1_1") (pintype "passive"))
      (node (ref "U7") (pin "4") (pinfunction "BP_4") (pintype "input"))
    )
    (net (code "62") (name "Net-(U7-EN)") (class "Default")
      (node (ref "C14") (pin "1") (pinfunction "1_1") (pintype "passive"))
      (node (ref "L11") (pin "2") (pinfunction "2_2") (pintype "passive"))
      (node (ref "U7") (pin "1") (pinfunction "IN_1") (pintype "input"))
      (node (ref "U7") (pin "3") (pinfunction "EN_3") (pintype "input"))
    )
    (net (code "63") (name "Net-(U11-C1)") (class "Default")
      (node (ref "C23") (pin "1") (pinfunction "1_1") (pintype "passive"))
      (node (ref "U11") (pin "10") (pinfunction "C1_10") (pintype "bidirectional"))
    )
    (net (code "64") (name "Net-(U11-SETC)") (class "Default")
      (node (ref "C24") (pin "2") (pinfunction "2_2") (pintype "passive"))
      (node (ref "U11") (pin "12") (pinfunction "SETC_12") (pintype "bidirectional"))
    )
    (net (code "65") (name "Net-(U11-SETP)") (class "Default")
      (node (ref "C24") (pin "1") (pinfunction "1_1") (pintype "passive"))
      (node (ref "U11") (pin "8") (pinfunction "SETP_8") (pintype "bidirectional"))
    )
    (net (code "66") (name "Net-(U12-PLLFILT)") (class "Default")
      (node (ref "C25") (pin "1") (pinfunction "1_1") (pintype "passive"))
      (node (ref "U12") (pin "14") (pinfunction "PLLFILT_14") (pintype "bidirectional"))
    )
    (net (code "67") (name "Net-(U13-CLK)") (class "Default")
      (node (ref "RN1") (pin "8") (pinfunction "8_8") (pintype "passive"))
      (node (ref "U13") (pin "P$5") (pinfunction "CLK_P$5") (pintype "bidirectional"))
    )
    (net (code "68") (name "Net-(U13-CS)") (class "Default")
      (node (ref "RN1") (pin "5") (pinfunction "5_5") (pintype "passive"))
      (node (ref "U13") (pin "P$2") (pinfunction "CS_P$2") (pintype "bidirectional"))
    )
    (net (code "69") (name "Net-(U13-DI)") (class "Default")
      (node (ref "RN1") (pin "6") (pinfunction "6_6") (pintype "passive"))
      (node (ref "U13") (pin "P$3") (pinfunction "DI_P$3") (pintype "bidirectional"))
    )
    (net (code "70") (name "Net-(U13-DO)") (class "Default")
      (node (ref "RN1") (pin "7") (pinfunction "7_7") (pintype "passive"))
      (node (ref "U13") (pin "P$7") (pinfunction "DO_P$7") (pintype "bidirectional"))
    )
    (net (code "71") (name "Net-(U14-CPOUT)") (class "Default")
      (node (ref "C20") (pin "1") (pinfunction "1_1") (pintype "passive"))
      (node (ref "U14") (pin "20") (pinfunction "CPOUT_20") (pintype "bidirectional"))
    )
    (net (code "72") (name "Net-(U14-INT)") (class "Default")
      (node (ref "JP6") (pin "2") (pinfunction "2_2") (pintype "passive"))
      (node (ref "U14") (pin "12") (pinfunction "INT_12") (pintype "bidirectional"))
    )
    (net (code "73") (name "Net-(U14-REGOUT)") (class "Default")
      (node (ref "C26") (pin "1") (pinfunction "1_1") (pintype "passive"))
      (node (ref "U14") (pin "10") (pinfunction "REGOUT_10") (pintype "bidirectional"))
    )
    (net (code "74") (name "OTG_FS_DM") (class "Default")
      (node (ref "R6") (pin "2") (pinfunction "2_2") (pintype "passive"))
      (node (ref "U1") (pin "44") (pinfunction "PA11_44") (pintype "bidirectional"))
    )
    (net (code "75") (name "OTG_FS_DP") (class "Default")
      (node (ref "R8") (pin "2") (pinfunction "2_2") (pintype "passive"))
      (node (ref "U1") (pin "45") (pinfunction "PA12_45") (pintype "bidirectional"))
    )
    (net (code "76") (name "PB2-BOOT1") (class "Default")
      (node (ref "R5") (pin "1") (pinfunction "1_1") (pintype "passive"))
      (node (ref "U1") (pin "28") (pinfunction "PB2_28") (pintype "bidirectional"))
    )
    (net (code "77") (name "PPM_INPUT") (class "Default")
      (node (ref "J2") (pin "23") (pinfunction "S_23") (pintype "passive"))
      (node (ref "J3") (pin "23") (pinfunction "S_23") (pintype "passive"))
      (node (ref "R10") (pin "1") (pinfunction "1_1") (pintype "passive"))
      (node (ref "U1") (pin "43") (pinfunction "PA10_43") (pintype "bidirectional"))
    )
    (net (code "78") (name "RESET") (class "Default")
      (node (ref "!RESET") (pin "P$1") (pinfunction "P$1_P$1") (pintype "passive"))
      (node (ref "C17") (pin "2") (pinfunction "2_2") (pintype "passive"))
      (node (ref "R16") (pin "1") (pinfunction "1_1") (pintype "passive"))
      (node (ref "S1") (pin "A1") (pinfunction "1_A1") (pintype "passive"))
      (node (ref "U1") (pin "7") (pinfunction "NRST_7") (pintype "input"))
    )
    (net (code "79") (name "SPI1_MISO") (class "Default")
      (node (ref "SPI1_MISO") (pin "P$1") (pinfunction "P$1_P$1") (pintype "passive"))
      (node (ref "U1") (pin "22") (pinfunction "PA6_22") (pintype "bidirectional"))
      (node (ref "U12") (pin "4") (pinfunction "SDO/SA0_4") (pintype "bidirectional"))
      (node (ref "U14") (pin "9") (pinfunction "AD0/SDO_9") (pintype "bidirectional"))
      (node (ref "U9") (pin "8") (pinfunction "SDO_8") (pintype "bidirectional"))
    )
    (net (code "80") (name "SPI1_MOSI") (class "Default")
      (node (ref "SPI1_MOSI") (pin "P$1") (pinfunction "P$1_P$1") (pintype "passive"))
      (node (ref "U1") (pin "23") (pinfunction "PA7_23") (pintype "bidirectional"))
      (node (ref "U12") (pin "3") (pinfunction "SDA/SDI/SDO_3") (pintype "bidirectional"))
      (node (ref "U14") (pin "24") (pinfunction "SDA/SDI_24") (pintype "bidirectional"))
      (node (ref "U9") (pin "9") (pinfunction "SDI_9") (pintype "bidirectional"))
    )
    (net (code "81") (name "SPI1_SCK") (class "Default")
      (node (ref "SPI1_SCK") (pin "P$1") (pinfunction "P$1_P$1") (pintype "passive"))
      (node (ref "U1") (pin "21") (pinfunction "PA5_21") (pintype "bidirectional"))
      (node (ref "U12") (pin "2") (pinfunction "SCL/SPC_2") (pintype "input"))
      (node (ref "U14") (pin "23") (pinfunction "SCL/SCLK_23") (pintype "bidirectional"))
      (node (ref "U9") (pin "7") (pinfunction "SCK_7") (pintype "bidirectional"))
    )
    (net (code "82") (name "SPI3_MISO") (class "Default")
      (node (ref "RN1") (pin "2") (pinfunction "2_2") (pintype "passive"))
      (node (ref "U1") (pin "52") (pinfunction "PC11_52") (pintype "bidirectional"))
    )
    (net (code "83") (name "SPI3_MOSI") (class "Default")
      (node (ref "RN1") (pin "3") (pinfunction "3_3") (pintype "passive"))
      (node (ref "U1") (pin "57") (pinfunction "PB5_57") (pintype "bidirectional"))
    )
    (net (code "84") (name "SPI3_NSS") (class "Default")
      (node (ref "RN1") (pin "4") (pinfunction "4_4") (pintype "passive"))
      (node (ref "U1") (pin "20") (pinfunction "PA4_20") (pintype "bidirectional"))
    )
    (net (code "85") (name "SPI3_SCK") (class "Default")
      (node (ref "RN1") (pin "1") (pinfunction "1_1") (pintype "passive"))
      (node (ref "U1") (pin "51") (pinfunction "PC10_51") (pintype "bidirectional"))
    )
    (net (code "86") (name "UART5_RX") (class "Default")
      (node (ref "J2") (pin "16") (pinfunction "S_16") (pintype "passive"))
      (node (ref "J3") (pin "16") (pinfunction "S_16") (pintype "passive"))
      (node (ref "U1") (pin "54") (pinfunction "PD2_54") (pintype "bidirectional"))
    )
    (net (code "87") (name "UART5_TX") (class "Default")
      (node (ref "J2") (pin "15") (pinfunction "S_15") (pintype "passive"))
      (node (ref "J3") (pin "15") (pinfunction "S_15") (pintype "passive"))
      (node (ref "U1") (pin "53") (pinfunction "PC12_53") (pintype "bidirectional"))
    )
    (net (code "88") (name "USART1_RX") (class "Default")
      (node (ref "U1") (pin "59") (pinfunction "PB7_59") (pintype "bidirectional"))
      (node (ref "U4") (pin "4") (pinfunction "A2_4") (pintype "bidirectional"))
    )
    (net (code "89") (name "USART1_RX_EXT") (class "Default")
      (node (ref "J1") (pin "7") (pinfunction "S_7") (pintype "passive"))
      (node (ref "J2") (pin "8") (pinfunction "S_8") (pintype "passive"))
      (node (ref "J3") (pin "8") (pinfunction "S_8") (pintype "passive"))
      (node (ref "U4") (pin "1") (pinfunction "B2_1") (pintype "bidirectional"))
    )
    (net (code "90") (name "USART1_TX") (class "Default")
      (node (ref "U1") (pin "58") (pinfunction "PB6_58") (pintype "bidirectional"))
      (node (ref "U4") (pin "5") (pinfunction "A1_5") (pintype "bidirectional"))
    )
    (net (code "91") (name "USART1_TX_EXT") (class "Default")
      (node (ref "J1") (pin "8") (pinfunction "S_8") (pintype "passive"))
      (node (ref "J2") (pin "7") (pinfunction "S_7") (pintype "passive"))
      (node (ref "J3") (pin "7") (pinfunction "S_7") (pintype "passive"))
      (node (ref "U4") (pin "8") (pinfunction "B1_8") (pintype "bidirectional"))
    )
    (net (code "92") (name "USART2_CTS") (class "Default")
      (node (ref "J2") (pin "19") (pinfunction "S_19") (pintype "passive"))
      (node (ref "J3") (pin "19") (pinfunction "S_19") (pintype "passive"))
      (node (ref "U1") (pin "14") (pinfunction "PA0_14") (pintype "bidirectional"))
      (node (ref "U2") (pin "5") (pinfunction "A1_5") (pintype "bidirectional"))
    )
    (net (code "93") (name "USART2_RTS") (class "Default")
      (node (ref "J2") (pin "20") (pinfunction "S_20") (pintype "passive"))
      (node (ref "J3") (pin "20") (pinfunction "S_20") (pintype "passive"))
      (node (ref "U1") (pin "15") (pinfunction "PA1_15") (pintype "bidirectional"))
      (node (ref "U2") (pin "4") (pinfunction "A2_4") (pintype "bidirectional"))
    )
    (net (code "94") (name "USART2_RX") (class "Default")
      (node (ref "J2") (pin "22") (pinfunction "S_22") (pintype "passive"))
      (node (ref "J3") (pin "22") (pinfunction "S_22") (pintype "passive"))
      (node (ref "U1") (pin "17") (pinfunction "PA3_17") (pintype "bidirectional"))
      (node (ref "U3") (pin "4") (pinfunction "A2_4") (pintype "bidirectional"))
    )
    (net (code "95") (name "USART2_TX") (class "Default")
      (node (ref "J2") (pin "21") (pinfunction "S_21") (pintype "passive"))
      (node (ref "J3") (pin "21") (pinfunction "S_21") (pintype "passive"))
      (node (ref "U1") (pin "16") (pinfunction "PA2_16") (pintype "bidirectional"))
      (node (ref "U3") (pin "5") (pinfunction "A1_5") (pintype "bidirectional"))
    )
    (net (code "96") (name "USART6_RX") (class "Default")
      (node (ref "J2") (pin "14") (pinfunction "S_14") (pintype "passive"))
      (node (ref "J3") (pin "14") (pinfunction "S_14") (pintype "passive"))
      (node (ref "L4") (pin "1") (pinfunction "1_1") (pintype "passive"))
      (node (ref "U1") (pin "38") (pinfunction "PC7_38") (pintype "bidirectional"))
      (node (ref "USART6_RX") (pin "P$1") (pinfunction "P$1_P$1") (pintype "passive"))
    )
    (net (code "97") (name "USART6_TX") (class "Default")
      (node (ref "J2") (pin "13") (pinfunction "S_13") (pintype "passive"))
      (node (ref "J3") (pin "13") (pinfunction "S_13") (pintype "passive"))
      (node (ref "L5") (pin "1") (pinfunction "1_1") (pintype "passive"))
      (node (ref "U1") (pin "37") (pinfunction "PC6_37") (pintype "bidirectional"))
      (node (ref "USART6_TX") (pin "P$1") (pinfunction "P$1_P$1") (pintype "passive"))
    )
    (net (code "98") (name "VBAT_IN") (class "Default")
      (node (ref "D2") (pin "1") (pinfunction "A1_1") (pintype "passive"))
      (node (ref "J1") (pin "5") (pinfunction "S_5") (pintype "passive"))
      (node (ref "L10") (pin "2") (pinfunction "2_2") (pintype "passive"))
    )
    (net (code "99") (name "VBUS") (class "Default")
      (node (ref "J5") (pin "VBUS") (pinfunction "1_VBUS") (pintype "power_in"))
      (node (ref "L8") (pin "2") (pinfunction "2_2") (pintype "passive"))
      (node (ref "U1") (pin "42") (pinfunction "PA9_42") (pintype "bidirectional"))
    )
    (net (code "100") (name "VDD_3V3") (class "Default")
      (node (ref "C10") (pin "1") (pinfunction "1_1") (pintype "passive"))
      (node (ref "C2") (pin "1") (pinfunction "1_1") (pintype "passive"))
      (node (ref "C6") (pin "A") (pinfunction "+_A") (pintype "passive"))
      (node (ref "C8") (pin "1") (pinfunction "1_1") (pintype "passive"))
      (node (ref "C9") (pin "1") (pinfunction "1_1") (pintype "passive"))
      (node (ref "F1") (pin "1") (pinfunction "1_1") (pintype "bidirectional"))
      (node (ref "J6") (pin "1") (pinfunction "S_1") (pintype "passive"))
      (node (ref "JP1") (pin "1") (pinfunction "1_1") (pintype "passive"))
      (node (ref "JP2") (pin "3") (pinfunction "3_3") (pintype "passive"))
      (node (ref "LED1") (pin "A") (pinfunction "A_A") (pintype "passive"))
      (node (ref "LED2") (pin "A") (pinfunction "A_A") (pintype "passive"))
      (node (ref "LED3") (pin "A") (pinfunction "A_A") (pintype "passive"))
      (node (ref "R16") (pin "2") (pinfunction "2_2") (pintype "passive"))
      (node (ref "R19") (pin "2") (pinfunction "2_2") (pintype "passive"))
      (node (ref "R20") (pin "2") (pinfunction "2_2") (pintype "passive"))
      (node (ref "R7") (pin "2") (pinfunction "2_2") (pintype "passive"))
      (node (ref "R9") (pin "2") (pinfunction "2_2") (pintype "passive"))
      (node (ref "U1") (pin "1") (pinfunction "VBAT_1") (pintype "power_in"))
      (node (ref "U1") (pin "19") (pinfunction "VDD_4_19") (pintype "power_in"))
      (node (ref "U1") (pin "32") (pinfunction "VDD_1_32") (pintype "power_in"))
      (node (ref "U1") (pin "48") (pinfunction "VDD_2_48") (pintype "power_in"))
      (node (ref "U1") (pin "64") (pinfunction "VDD_3_64") (pintype "power_in"))
      (node (ref "U12") (pin "1") (pinfunction "VDD_IO_1") (pintype "bidirectional"))
      (node (ref "U13") (pin "P$4") (pinfunction "VCC_P$4") (pintype "passive"))
      (node (ref "U2") (pin "3") (pinfunction "VCCA_3") (pintype "input"))
      (node (ref "U2") (pin "6") (pinfunction "OE_6") (pintype "input"))
      (node (ref "U3") (pin "3") (pinfunction "VCCA_3") (pintype "input"))
      (node (ref "U3") (pin "6") (pinfunction "OE_6") (pintype "input"))
      (node (ref "U4") (pin "3") (pinfunction "VCCA_3") (pintype "input"))
      (node (ref "U4") (pin "6") (pinfunction "OE_6") (pintype "input"))
      (node (ref "U4") (pin "7") (pinfunction "VCCB_7") (pintype "input"))
      (node (ref "U5") (pin "1") (pinfunction "VCCA_1") (pintype "passive"))
      (node (ref "U6") (pin "2") (pinfunction "VOUT_2") (pintype "bidirectional"))
      (node (ref "U6") (pin "4") (pinfunction "VOUT-TAB_4") (pintype "bidirectional"))
      (node (ref "U8") (pin "8") (pinfunction "VCC_8") (pintype "power_in"))
      (node (ref "U9") (pin "10") (pinfunction "VDDIO_10") (pintype "bidirectional"))
      (node (ref "VDD_3V3") (pin "P$1") (pinfunction "P$1_P$1") (pintype "passive"))
    )
    (net (code "101") (name "VDD_3V3_ANALOG") (class "Default")
      (node (ref "C13") (pin "A") (pinfunction "+_A") (pintype "passive"))
      (node (ref "C15") (pin "1") (pinfunction "1_1") (pintype "passive"))
      (node (ref "C18") (pin "1") (pinfunction "1_1") (pintype "passive"))
      (node (ref "C19") (pin "1") (pinfunction "1_1") (pintype "passive"))
      (node (ref "C21") (pin "1") (pinfunction "1_1") (pintype "passive"))
      (node (ref "C22") (pin "1") (pinfunction "1_1") (pintype "passive"))
      (node (ref "C28") (pin "1") (pinfunction "1_1") (pintype "passive"))
      (node (ref "U1") (pin "13") (pinfunction "VDDA_13") (pintype "power_in"))
      (node (ref "U10") (pin "1") (pinfunction "VDD_1") (pintype "bidirectional"))
      (node (ref "U10") (pin "2") (pinfunction "PS_2") (pintype "bidirectional"))
      (node (ref "U10") (pin "4") (pinfunction "CSB1_4") (pintype "bidirectional"))
      (node (ref "U10") (pin "5") (pinfunction "CSB2_5") (pintype "bidirectional"))
      (node (ref "U11") (pin "13") (pinfunction "VDDIO_13") (pintype "bidirectional"))
      (node (ref "U11") (pin "2") (pinfunction "VDD_2") (pintype "bidirectional"))
      (node (ref "U11") (pin "4") (pinfunction "S1_VDDIO_4") (pintype "bidirectional"))
      (node (ref "U12") (pin "15") (pinfunction "RES_P15_VDD_15") (pintype "bidirectional"))
      (node (ref "U12") (pin "16") (pinfunction "VDD_16") (pintype "bidirectional"))
      (node (ref "U14") (pin "13") (pinfunction "VDD_13") (pintype "bidirectional"))
      (node (ref "U7") (pin "5") (pinfunction "OUT_5") (pintype "passive"))
      (node (ref "U9") (pin "2") (pinfunction "VDD_2") (pintype "bidirectional"))
      (node (ref "VDDA_3V3") (pin "P$1") (pinfunction "P$1_P$1") (pintype "passive"))
    )
    (net (code "102") (name "VDD_5V") (class "Default")
      (node (ref "C27") (pin "A") (pinfunction "+_A") (pintype "passive"))
      (node (ref "C7") (pin "1") (pinfunction "1_1") (pintype "passive"))
      (node (ref "D2") (pin "2") (pinfunction "A2_2") (pintype "passive"))
      (node (ref "JP1") (pin "3") (pinfunction "3_3") (pintype "passive"))
      (node (ref "JP2") (pin "1") (pinfunction "1_1") (pintype "passive"))
      (node (ref "L1") (pin "1") (pinfunction "1_1") (pintype "passive"))
      (node (ref "L11") (pin "1") (pinfunction "1_1") (pintype "passive"))
      (node (ref "Q1") (pin "4") (pinfunction "S_4") (pintype "passive"))
      (node (ref "R1") (pin "2") (pinfunction "2_2") (pintype "passive"))
      (node (ref "R2") (pin "2") (pinfunction "2_2") (pintype "passive"))
      (node (ref "U6") (pin "3") (pinfunction "VIN_3") (pintype "bidirectional"))
    )
    (net (code "103") (name "VDD_5V_IN") (class "Default")
      (node (ref "D1") (pin "CATHODE") (pinfunction "C_CATHODE") (pintype "passive"))
      (node (ref "J2") (pin "1") (pinfunction "S_1") (pintype "passive"))
      (node (ref "J2") (pin "2") (pinfunction "S_2") (pintype "passive"))
      (node (ref "J3") (pin "1") (pinfunction "S_1") (pintype "passive"))
      (node (ref "J3") (pin "2") (pinfunction "S_2") (pintype "passive"))
      (node (ref "Q1") (pin "1") (pinfunction "D_1") (pintype "passive"))
      (node (ref "Q1") (pin "2") (pinfunction "D1_2") (pintype "passive"))
      (node (ref "Q1") (pin "5") (pinfunction "D2_5") (pintype "passive"))
      (node (ref "Q1") (pin "6") (pinfunction "D3_6") (pintype "passive"))
    )
    (net (code "104") (name "VDD_IO") (class "Default")
      (node (ref "C1") (pin "1") (pinfunction "1_1") (pintype "passive"))
      (node (ref "JP1") (pin "2") (pinfunction "2_2") (pintype "passive"))
      (node (ref "U2") (pin "7") (pinfunction "VCCB_7") (pintype "input"))
      (node (ref "U3") (pin "7") (pinfunction "VCCB_7") (pintype "input"))
      (node (ref "U5") (pin "8") (pinfunction "VCCB_8") (pintype "passive"))
    )
    (net (code "105") (name "unconnected-(J4D-S-Pad4)") (class "Default")
      (node (ref "J4") (pin "4") (pinfunction "S_4") (pintype "passive"))
    )
    (net (code "106") (name "unconnected-(J5-4-PadID)") (class "Default")
      (node (ref "J5") (pin "ID") (pinfunction "4_ID") (pintype "passive"))
    )
    (net (code "107") (name "unconnected-(U8-WP-Pad7)") (class "Default")
      (node (ref "U8") (pin "7") (pinfunction "WP_7") (pintype "bidirectional"))
    )
    (net (code "108") (name "unconnected-(U9-INT-Pad4)") (class "Default")
      (node (ref "U9") (pin "4") (pinfunction "INT_4") (pintype "bidirectional"))
    )
    (net (code "109") (name "unconnected-(U9-NC-Pad1)") (class "Default")
      (node (ref "U9") (pin "1") (pinfunction "NC_1") (pintype "bidirectional"))
    )
    (net (code "110") (name "unconnected-(U9-NC1-Pad6)") (class "Default")
      (node (ref "U9") (pin "6") (pinfunction "NC1_6") (pintype "bidirectional"))
    )
    (net (code "111") (name "unconnected-(U9-NC2-Pad11)") (class "Default")
      (node (ref "U9") (pin "11") (pinfunction "NC2_11") (pintype "bidirectional"))
    )
    (net (code "112") (name "unconnected-(U9-NC3-Pad12)") (class "Default")
      (node (ref "U9") (pin "12") (pinfunction "NC3_12") (pintype "bidirectional"))
    )
    (net (code "113") (name "unconnected-(U10-SDO-Pad6)") (class "Default")
      (node (ref "U10") (pin "6") (pinfunction "SDO_6") (pintype "bidirectional"))
    )
    (net (code "114") (name "unconnected-(U11-NC_P3-Pad3)") (class "Default")
      (node (ref "U11") (pin "3") (pinfunction "NC_P3_3") (pintype "no_connect"))
    )
    (net (code "115") (name "unconnected-(U11-NC_P5-Pad5)") (class "Default")
      (node (ref "U11") (pin "5") (pinfunction "NC_P5_5") (pintype "no_connect"))
    )
    (net (code "116") (name "unconnected-(U11-NC_P6-Pad6)") (class "Default")
      (node (ref "U11") (pin "6") (pinfunction "NC_P6_6") (pintype "no_connect"))
    )
    (net (code "117") (name "unconnected-(U11-NC_P7-Pad7)") (class "Default")
      (node (ref "U11") (pin "7") (pinfunction "NC_P7_7") (pintype "no_connect"))
    )
    (net (code "118") (name "unconnected-(U11-NC_P14-Pad14)") (class "Default")
      (node (ref "U11") (pin "14") (pinfunction "NC_P14_14") (pintype "no_connect"))
    )
    (net (code "119") (name "unconnected-(U12-DRDY{slash}INT2-Pad6)") (class "Default")
      (node (ref "U12") (pin "6") (pinfunction "DRDY/INT2_6") (pintype "output"))
    )
    (net (code "120") (name "unconnected-(U12-INT1-Pad7)") (class "Default")
      (node (ref "U12") (pin "7") (pinfunction "INT1_7") (pintype "output"))
    )
    (net (code "121") (name "unconnected-(U14-AUX_CL-Pad7)") (class "Default")
      (node (ref "U14") (pin "7") (pinfunction "AUX_CL_7") (pintype "bidirectional"))
    )
    (net (code "122") (name "unconnected-(U14-AUX_DA-Pad6)") (class "Default")
      (node (ref "U14") (pin "6") (pinfunction "AUX_DA_6") (pintype "bidirectional"))
    )
    (net (code "123") (name "unconnected-(U14-CLKOUT-Pad22)") (class "Default")
      (node (ref "U14") (pin "22") (pinfunction "CLKOUT_22") (pintype "bidirectional"))
    )
    (net (code "124") (name "unconnected-(U14-NC1-Pad2)") (class "Default")
      (node (ref "U14") (pin "2") (pinfunction "NC1_2") (pintype "bidirectional"))
    )
    (net (code "125") (name "unconnected-(U14-NC2-Pad3)") (class "Default")
      (node (ref "U14") (pin "3") (pinfunction "NC2_3") (pintype "bidirectional"))
    )
    (net (code "126") (name "unconnected-(U14-NC3-Pad4)") (class "Default")
      (node (ref "U14") (pin "4") (pinfunction "NC3_4") (pintype "bidirectional"))
    )
    (net (code "127") (name "unconnected-(U14-NC4-Pad5)") (class "Default")
      (node (ref "U14") (pin "5") (pinfunction "NC4_5") (pintype "bidirectional"))
    )
    (net (code "128") (name "unconnected-(U14-NC5-Pad14)") (class "Default")
      (node (ref "U14") (pin "14") (pinfunction "NC5_14") (pintype "bidirectional"))
    )
    (net (code "129") (name "unconnected-(U14-NC6-Pad15)") (class "Default")
      (node (ref "U14") (pin "15") (pinfunction "NC6_15") (pintype "bidirectional"))
    )
    (net (code "130") (name "unconnected-(U14-NC7-Pad16)") (class "Default")
      (node (ref "U14") (pin "16") (pinfunction "NC7_16") (pintype "bidirectional"))
    )
    (net (code "131") (name "unconnected-(U14-NC8-Pad17)") (class "Default")
      (node (ref "U14") (pin "17") (pinfunction "NC8_17") (pintype "bidirectional"))
    )
    (net (code "132") (name "unconnected-(U14-RESV1-Pad19)") (class "Default")
      (node (ref "U14") (pin "19") (pinfunction "RESV1_19") (pintype "bidirectional"))
    )
    (net (code "133") (name "unconnected-(U14-RESV2-Pad21)") (class "Default")
      (node (ref "U14") (pin "21") (pinfunction "RESV2_21") (pintype "bidirectional"))
    )
    (net (code "134") (name "~{JTRST}") (class "Default")
      (node (ref "!JTRST") (pin "P$1") (pinfunction "P$1_P$1") (pintype "passive"))
      (node (ref "J6") (pin "10") (pinfunction "S_10") (pintype "passive"))
      (node (ref "U1") (pin "56") (pinfunction "PB4_56") (pintype "bidirectional"))
    )
  )
)
